# ProProject_NAFA_AstrAlim_2024-01-08.net
KiCad netlist of a schematic drawn in EasyEDA Pro
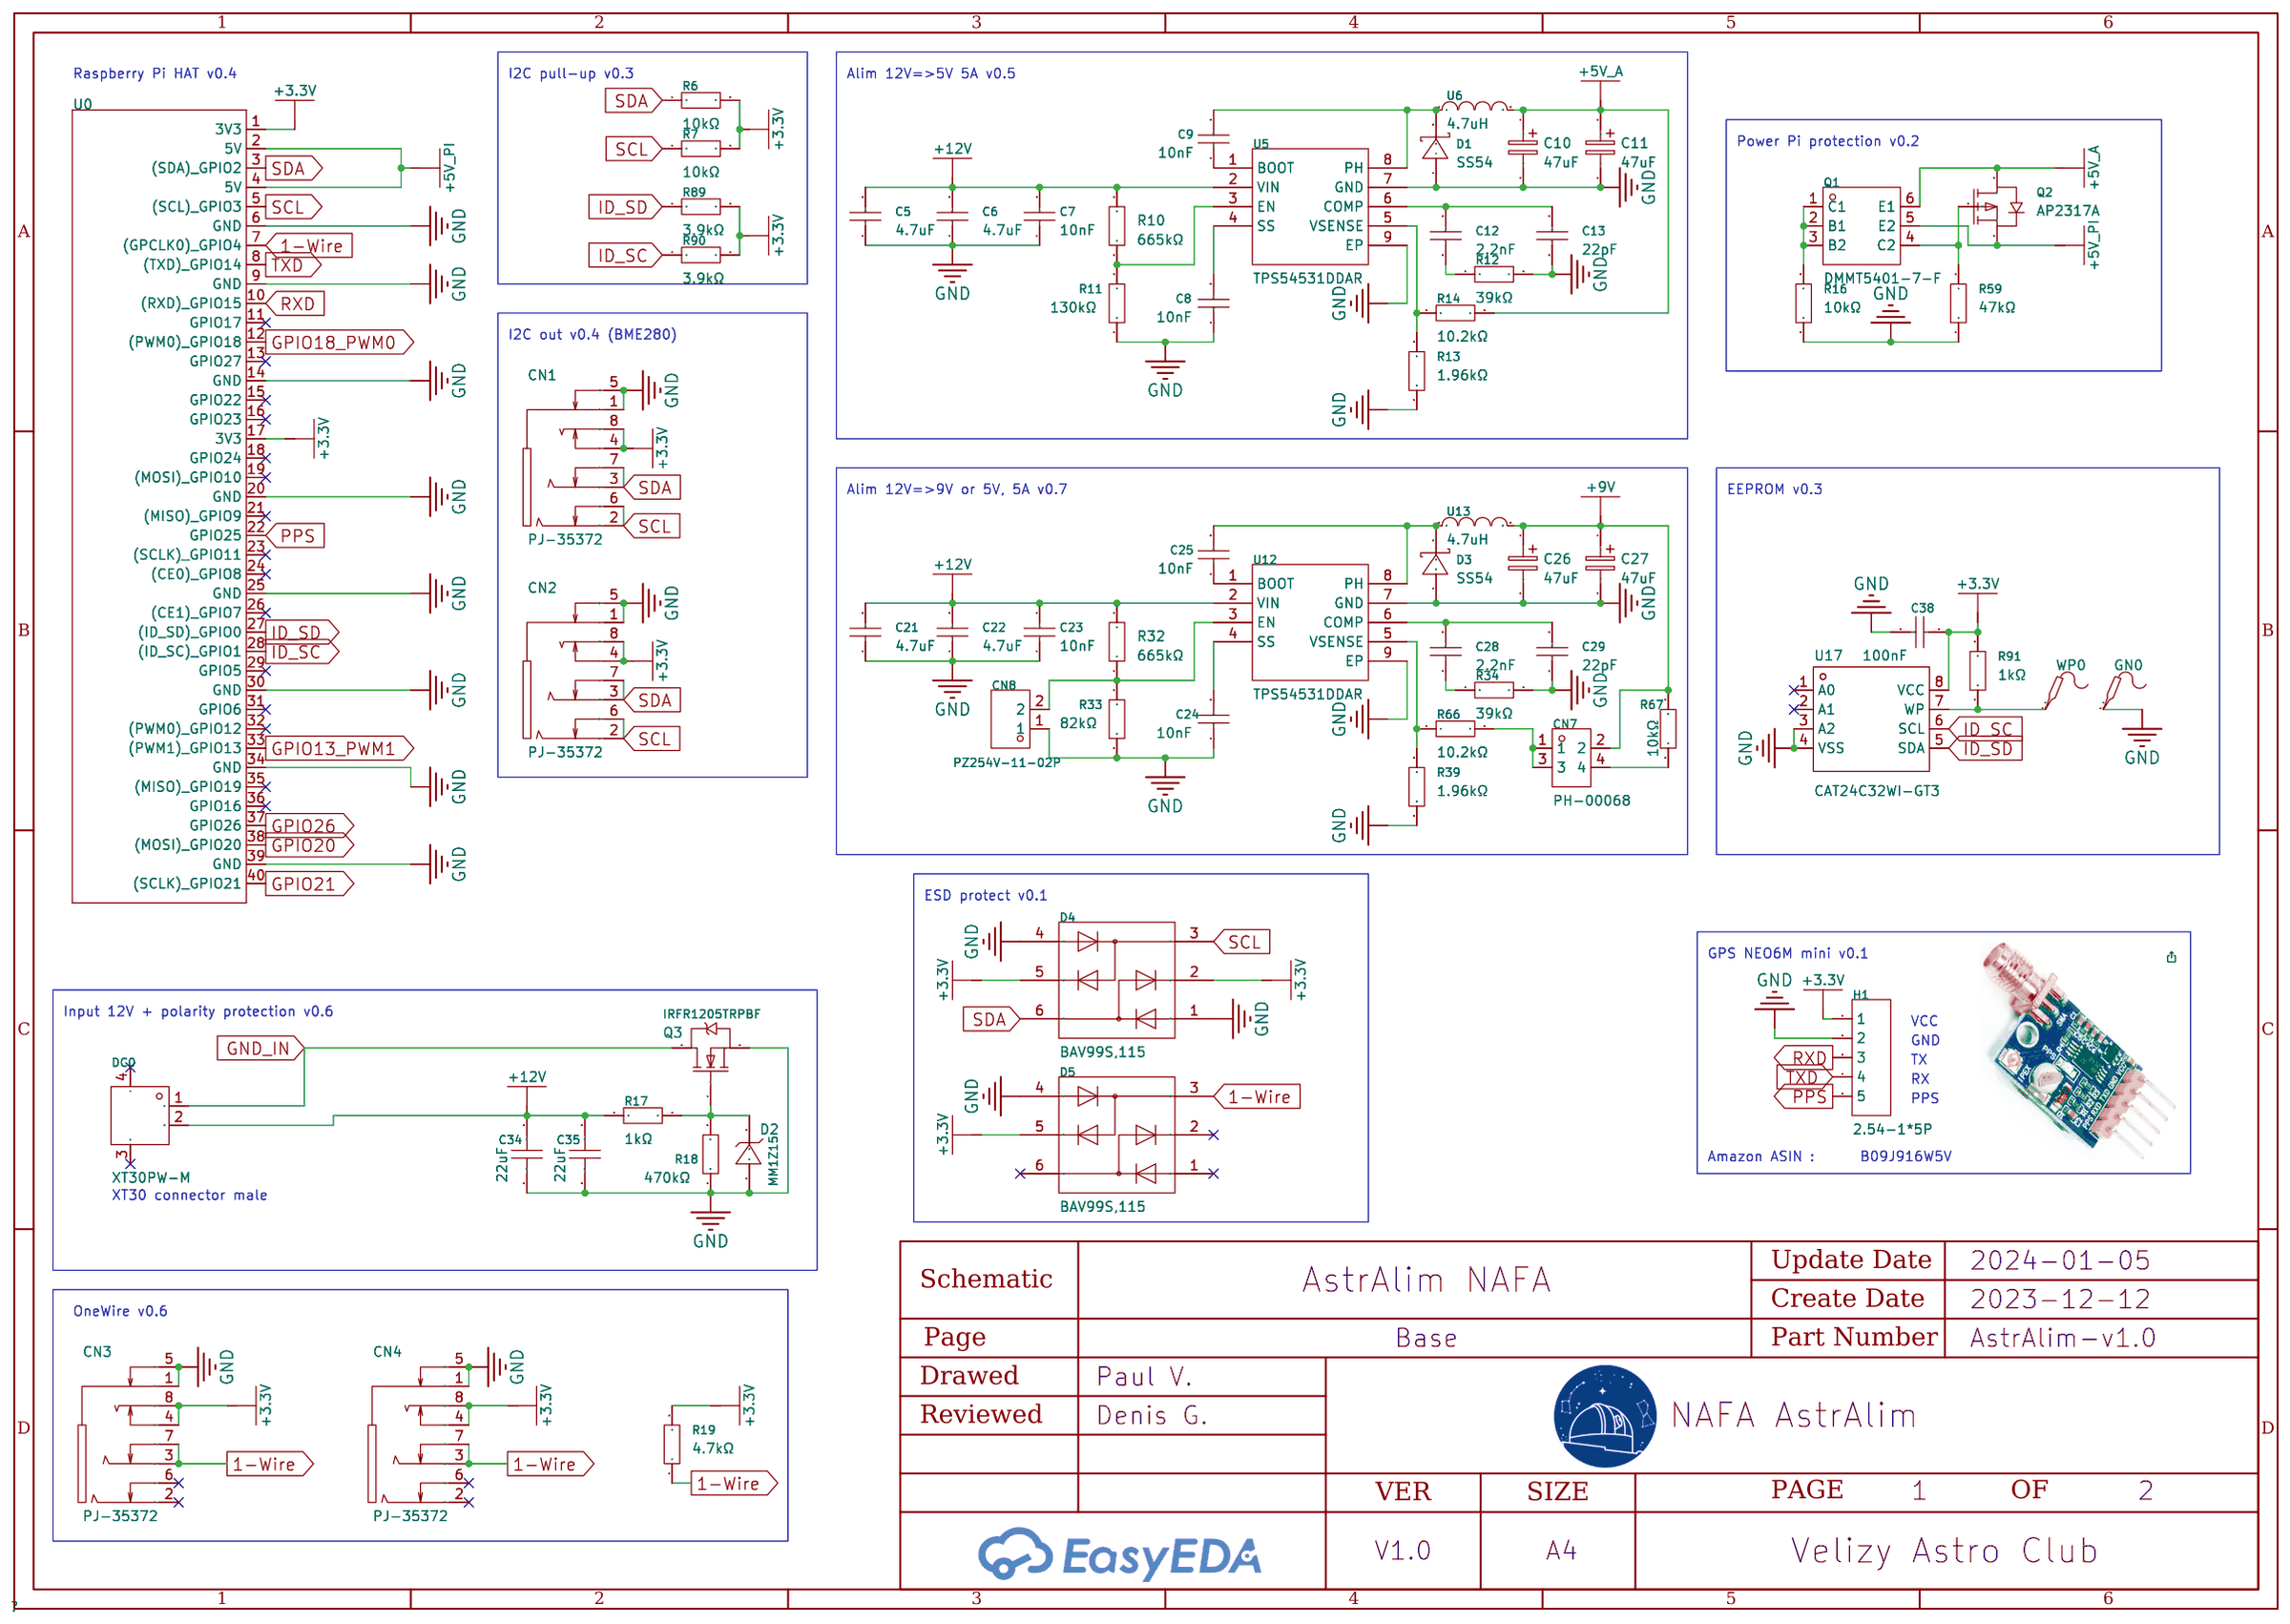
[diagram p0: Base]
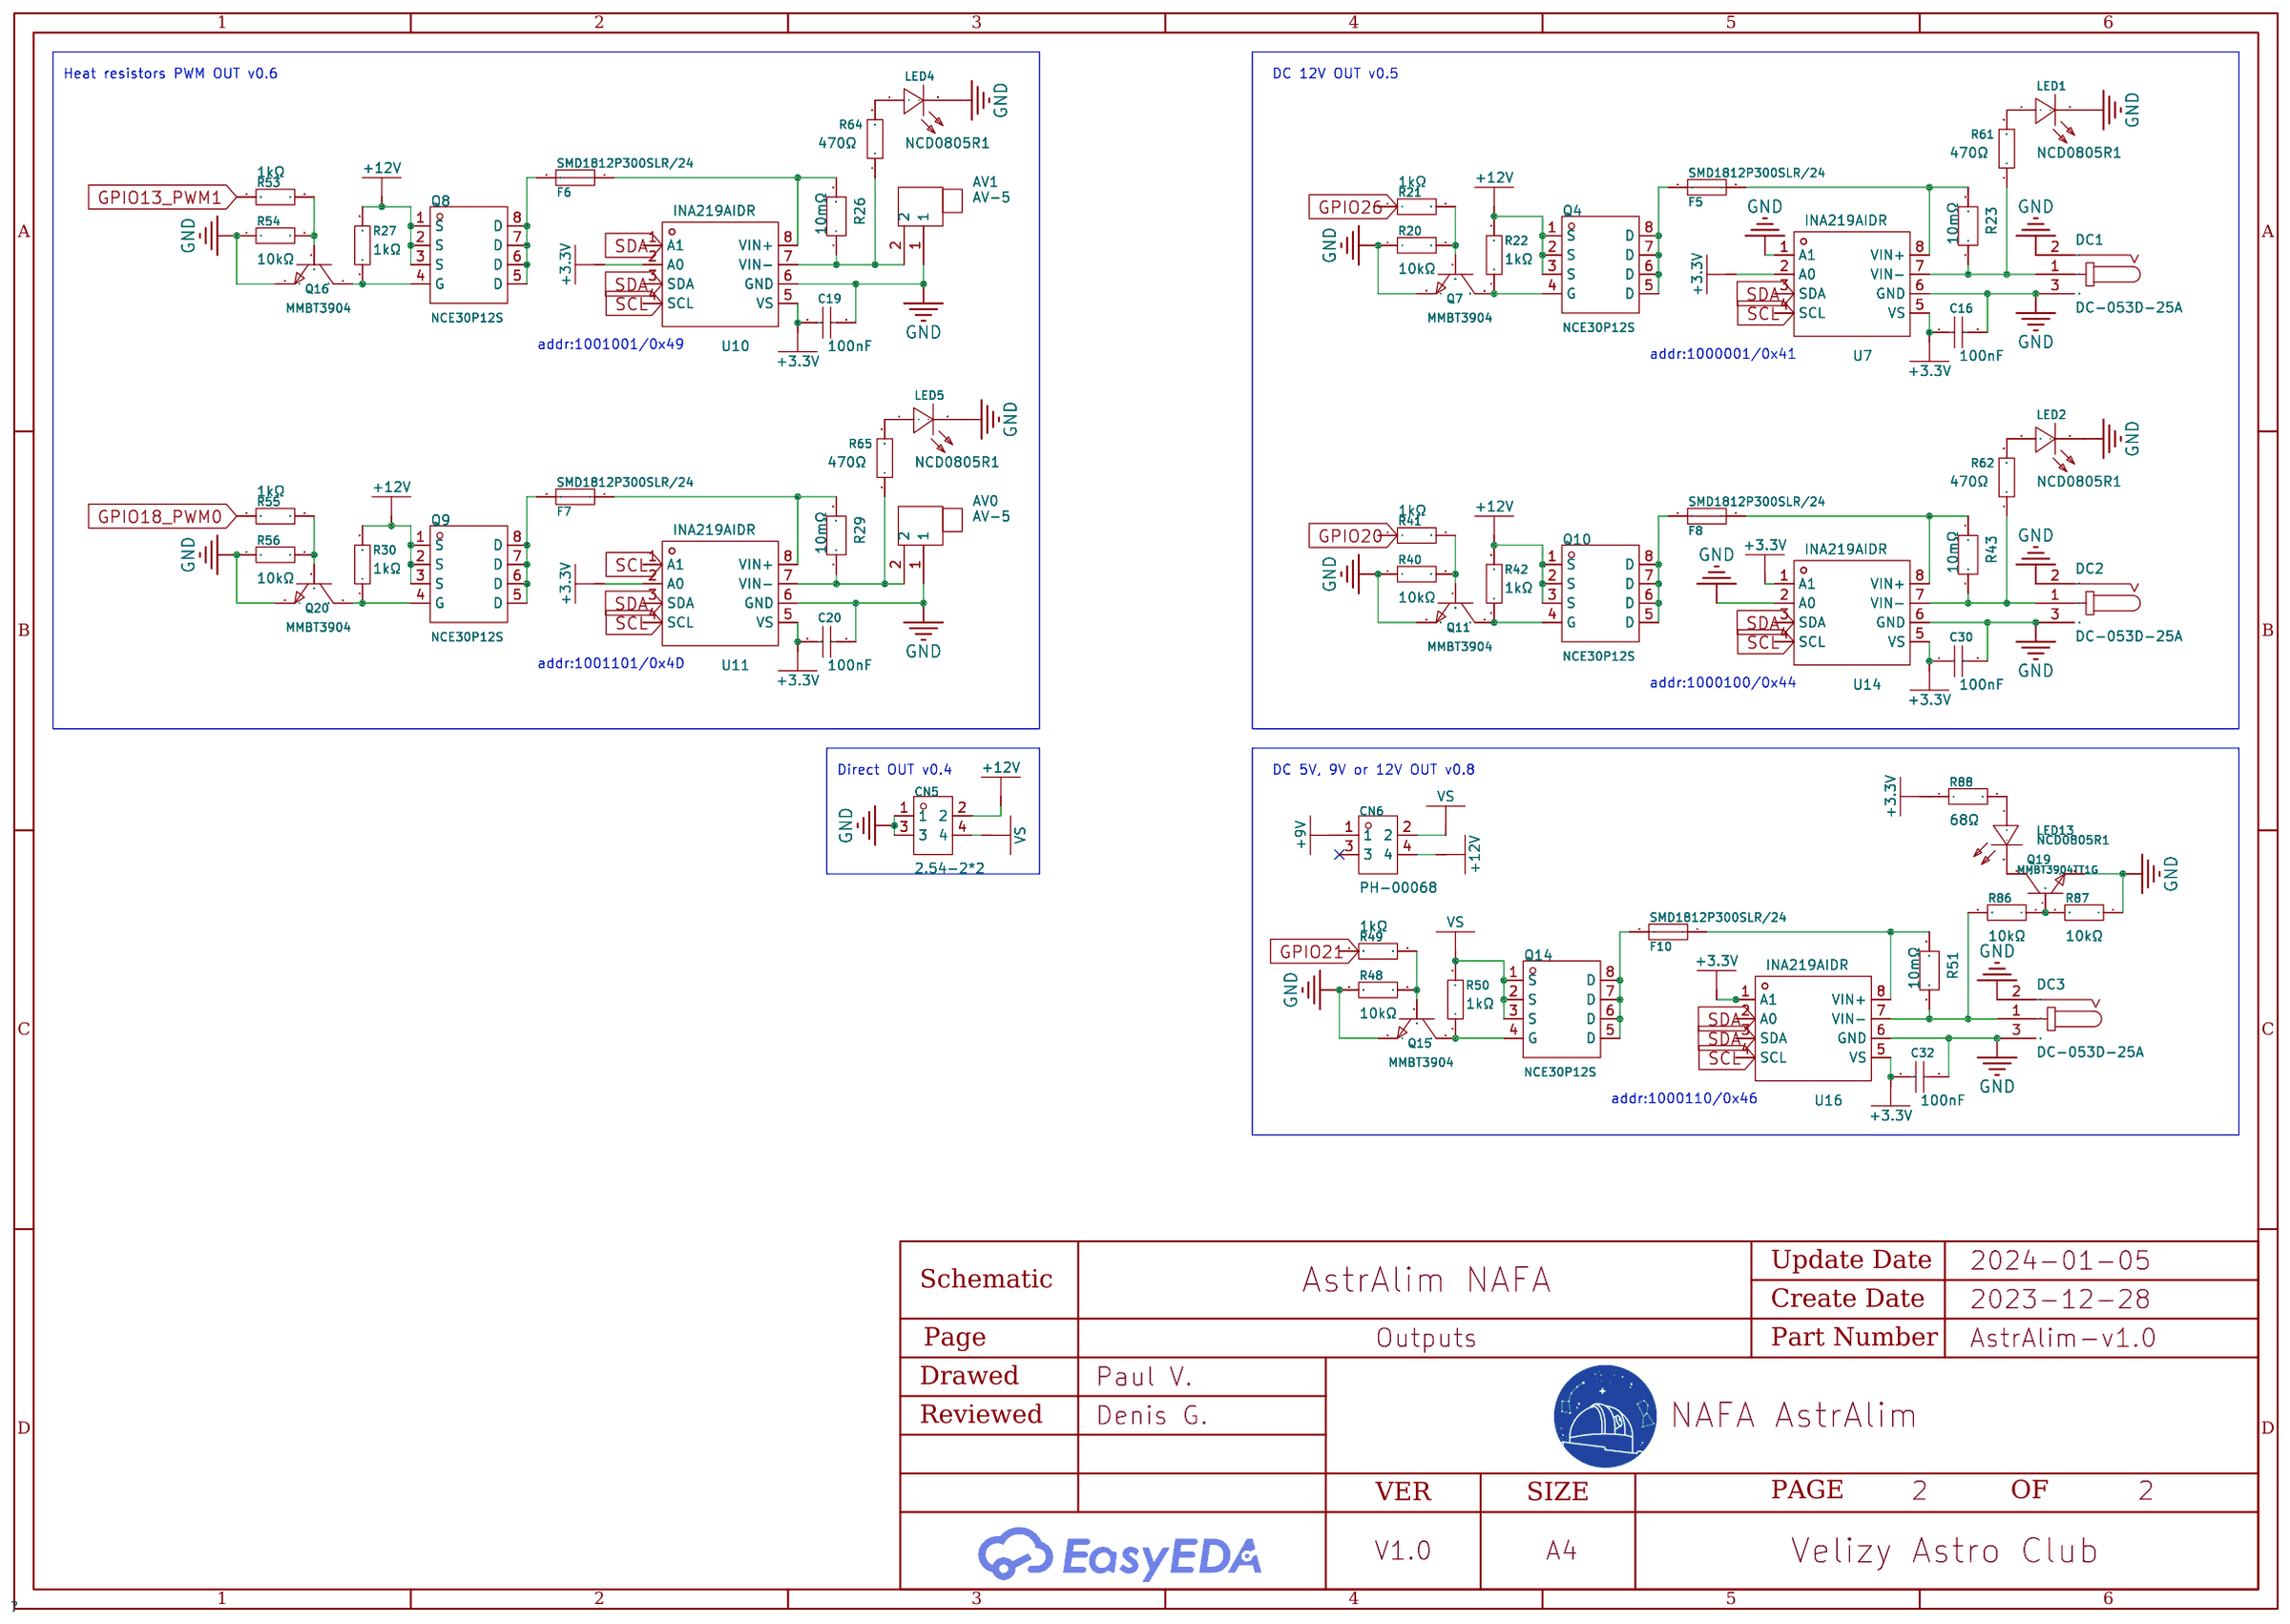
[diagram p1: Outputs]

(export (version "E")
  (design (tool "Eeschema 10.0.6"))
  (components
    (comp (ref "C5")
      (value "4.7uF")
      (footprint "easyedapro:C0805")
      (fields
        (field (name "Manufacturer Part") "CL21A475KAQNNNE")
        (field (name "Manufacturer") "SAMSUNG(三星)")
      )
      (libsource (lib "easyedapro") (part "CL21A475KAQNNNE"))
    )
    (comp (ref "C6")
      (value "4.7uF")
      (footprint "easyedapro:C0805")
      (fields
        (field (name "Manufacturer Part") "CL21A475KAQNNNE")
        (field (name "Manufacturer") "SAMSUNG(三星)")
      )
      (libsource (lib "easyedapro") (part "CL21A475KAQNNNE"))
    )
    (comp (ref "C7")
      (value "10nF")
      (footprint "easyedapro:C0402")
      (fields
        (field (name "Manufacturer Part") "CL05B103KB5NNNC")
        (field (name "Manufacturer") "SAMSUNG(三星)")
      )
      (libsource (lib "easyedapro") (part "CL05B103KB5NNNC"))
    )
    (comp (ref "C8")
      (value "10nF")
      (footprint "easyedapro:C0402")
      (fields
        (field (name "Manufacturer Part") "CL05B103KB5NNNC")
        (field (name "Manufacturer") "SAMSUNG(三星)")
      )
      (libsource (lib "easyedapro") (part "CL05B103KB5NNNC"))
    )
    (comp (ref "C9")
      (value "10nF")
      (footprint "easyedapro:C0402")
      (fields
        (field (name "Manufacturer Part") "CL05B103KB5NNNC")
        (field (name "Manufacturer") "SAMSUNG(三星)")
      )
      (libsource (lib "easyedapro") (part "CL05B103KB5NNNC"))
    )
    (comp (ref "C10")
      (value "47uF")
      (footprint "easyedapro:CAP-SMD_L3.5-W2.8-R-RD")
      (fields
        (field (name "Manufacturer Part") "CA45-B-16V-47uF-K")
        (field (name "Manufacturer") "CEC(振华新云)")
      )
      (libsource (lib "easyedapro") (part "CA45-B-16V-47UF-K"))
    )
    (comp (ref "C11")
      (value "47uF")
      (footprint "easyedapro:CAP-SMD_L3.5-W2.8-R-RD")
      (fields
        (field (name "Manufacturer Part") "CA45-B-16V-47uF-K")
        (field (name "Manufacturer") "CEC(振华新云)")
      )
      (libsource (lib "easyedapro") (part "CA45-B-16V-47UF-K"))
    )
    (comp (ref "C12")
      (value "2.2nF")
      (footprint "easyedapro:C0603")
      (fields (field (name "Manufacturer Part") "0603B222K500NT") (field (name "Manufacturer") "FH(风华)"))
      (libsource (lib "easyedapro") (part "0603B222K500NT"))
    )
    (comp (ref "C13")
      (value "22pF")
      (footprint "easyedapro:C0402")
      (fields (field (name "Manufacturer Part") "0402CG220J500NT") (field (name "Manufacturer") "FH(风华)"))
      (libsource (lib "easyedapro") (part "0402CG220J500NT"))
    )
    (comp (ref "C21")
      (value "4.7uF")
      (footprint "easyedapro:C0805")
      (fields
        (field (name "Manufacturer Part") "CL21A475KAQNNNE")
        (field (name "Manufacturer") "SAMSUNG(三星)")
      )
      (libsource (lib "easyedapro") (part "CL21A475KAQNNNE"))
    )
    (comp (ref "C22")
      (value "4.7uF")
      (footprint "easyedapro:C0805")
      (fields
        (field (name "Manufacturer Part") "CL21A475KAQNNNE")
        (field (name "Manufacturer") "SAMSUNG(三星)")
      )
      (libsource (lib "easyedapro") (part "CL21A475KAQNNNE"))
    )
    (comp (ref "C23")
      (value "10nF")
      (footprint "easyedapro:C0402")
      (fields
        (field (name "Manufacturer Part") "CL05B103KB5NNNC")
        (field (name "Manufacturer") "SAMSUNG(三星)")
      )
      (libsource (lib "easyedapro") (part "CL05B103KB5NNNC"))
    )
    (comp (ref "C24")
      (value "10nF")
      (footprint "easyedapro:C0402")
      (fields
        (field (name "Manufacturer Part") "CL05B103KB5NNNC")
        (field (name "Manufacturer") "SAMSUNG(三星)")
      )
      (libsource (lib "easyedapro") (part "CL05B103KB5NNNC"))
    )
    (comp (ref "C25")
      (value "10nF")
      (footprint "easyedapro:C0402")
      (fields
        (field (name "Manufacturer Part") "CL05B103KB5NNNC")
        (field (name "Manufacturer") "SAMSUNG(三星)")
      )
      (libsource (lib "easyedapro") (part "CL05B103KB5NNNC"))
    )
    (comp (ref "C26")
      (value "47uF")
      (footprint "easyedapro:CAP-SMD_L3.5-W2.8-R-RD")
      (fields
        (field (name "Manufacturer Part") "CA45-B-16V-47uF-K")
        (field (name "Manufacturer") "CEC(振华新云)")
      )
      (libsource (lib "easyedapro") (part "CA45-B-16V-47UF-K"))
    )
    (comp (ref "C27")
      (value "47uF")
      (footprint "easyedapro:CAP-SMD_L3.5-W2.8-R-RD")
      (fields
        (field (name "Manufacturer Part") "CA45-B-16V-47uF-K")
        (field (name "Manufacturer") "CEC(振华新云)")
      )
      (libsource (lib "easyedapro") (part "CA45-B-16V-47UF-K"))
    )
    (comp (ref "C28")
      (value "2.2nF")
      (footprint "easyedapro:C0603")
      (fields (field (name "Manufacturer Part") "0603B222K500NT") (field (name "Manufacturer") "FH(风华)"))
      (libsource (lib "easyedapro") (part "0603B222K500NT"))
    )
    (comp (ref "C29")
      (value "22pF")
      (footprint "easyedapro:C0402")
      (fields (field (name "Manufacturer Part") "0402CG220J500NT") (field (name "Manufacturer") "FH(风华)"))
      (libsource (lib "easyedapro") (part "0402CG220J500NT"))
    )
    (comp (ref "C34")
      (value "22uF")
      (footprint "easyedapro:C0805")
      (fields
        (field (name "Manufacturer Part") "CL21A226MAQNNNE")
        (field (name "Manufacturer") "SAMSUNG(三星)")
      )
      (libsource (lib "easyedapro") (part "CL21A226MAQNNNE"))
    )
    (comp (ref "C35")
      (value "22uF")
      (footprint "easyedapro:C0805")
      (fields
        (field (name "Manufacturer Part") "CL21A226MAQNNNE")
        (field (name "Manufacturer") "SAMSUNG(三星)")
      )
      (libsource (lib "easyedapro") (part "CL21A226MAQNNNE"))
    )
    (comp (ref "C38")
      (value "100nF")
      (footprint "easyedapro:C0402")
      (fields
        (field (name "Manufacturer Part") "CL05B104KO5NNNC")
        (field (name "Manufacturer") "SAMSUNG(三星)")
      )
      (libsource (lib "easyedapro") (part "CL05B104KO5NNNC"))
    )
    (comp (ref "CN1")
      (value "PJ-35372")
      (footprint "easyedapro:AUDIO-TH_PJ-35372")
      (fields (field (name "Manufacturer") "XKB Connectivity(中国星坤)"))
      (libsource (lib "easyedapro") (part "PJ-35372"))
    )
    (comp (ref "CN2")
      (value "PJ-35372")
      (footprint "easyedapro:AUDIO-TH_PJ-35372")
      (fields (field (name "Manufacturer") "XKB Connectivity(中国星坤)"))
      (libsource (lib "easyedapro") (part "PJ-35372"))
    )
    (comp (ref "CN3")
      (value "PJ-35372")
      (footprint "easyedapro:AUDIO-TH_PJ-35372")
      (fields (field (name "Manufacturer") "XKB Connectivity(中国星坤)"))
      (libsource (lib "easyedapro") (part "PJ-35372"))
    )
    (comp (ref "CN4")
      (value "PJ-35372")
      (footprint "easyedapro:AUDIO-TH_PJ-35372")
      (fields (field (name "Manufacturer") "XKB Connectivity(中国星坤)"))
      (libsource (lib "easyedapro") (part "PJ-35372"))
    )
    (comp (ref "CN7")
      (value "PH-00068")
      (footprint "easyedapro:HDR-TH_4P-P2.54-V-M-R2-C2-S2.54")
      (fields (field (name "Manufacturer") "Liansheng(连盛)"))
      (libsource (lib "easyedapro") (part "PH-00068"))
    )
    (comp (ref "CN8")
      (value "PZ254V-11-02P")
      (footprint "easyedapro:HDR-TH_2P-P2.54-V-M")
      (fields (field (name "Manufacturer") "XFCN(兴飞)"))
      (libsource (lib "easyedapro") (part "PZ254V-11-02P"))
    )
    (comp (ref "D1")
      (value "SS54")
      (footprint "easyedapro:SMA_L4.4-W2.8-LS5.4-R-RD")
      (fields (field (name "Manufacturer") "MDD"))
      (libsource (lib "easyedapro") (part "SS54_C22452"))
    )
    (comp (ref "D2")
      (value "MM1Z15")
      (footprint "easyedapro:SOD-123_L2.7-W1.6-LS3.7-RD")
      (fields (field (name "Manufacturer") "ST(先科)"))
      (libsource (lib "easyedapro") (part "MM1Z15"))
    )
    (comp (ref "D3")
      (value "SS54")
      (footprint "easyedapro:SMA_L4.4-W2.8-LS5.4-R-RD")
      (fields (field (name "Manufacturer") "MDD"))
      (libsource (lib "easyedapro") (part "SS54_C22452"))
    )
    (comp (ref "D4")
      (value "BAV99S,115")
      (footprint "easyedapro:SOT-363_L2.0-W1.3-P0.65-LS2.1-TL")
      (fields (field (name "Manufacturer") "Nexperia(安世)"))
      (libsource (lib "easyedapro") (part "BAV99S,135"))
    )
    (comp (ref "D5")
      (value "BAV99S,115")
      (footprint "easyedapro:SOT-363_L2.0-W1.3-P0.65-LS2.1-TL")
      (fields (field (name "Manufacturer") "Nexperia(安世)"))
      (libsource (lib "easyedapro") (part "BAV99S,135"))
    )
    (comp (ref "DC0")
      (value "XT30PW-M")
      (footprint "easyedapro:CONN-TH_XT30PW-F-1")
      (fields (field (name "Manufacturer") "AMASS(艾迈斯)"))
      (libsource (lib "easyedapro") (part "XT30PW-F"))
    )
    (comp (ref "GN0")
      (value "~")
      (footprint "easyedapro:Test-Point-0.5mm")
      (description "Test Point 测试点")
      (libsource (lib "easyedapro") (part "Test-Point"))
    )
    (comp (ref "H1")
      (value "2.54-1*5P")
      (footprint "easyedapro:HDR-TH_5P-P2.54-V-F")
      (fields (field (name "Manufacturer") "BOOMELE(博穆精密)"))
      (libsource (lib "easyedapro") (part "Header-Female-2.54_1x5"))
    )
    (comp (ref "Q1")
      (value "DMMT5401-7-F")
      (footprint "easyedapro:SOT-23-6_L2.9-W1.6-P0.95-LS2.8-BR")
      (fields (field (name "Manufacturer") "DIODES(美台)"))
      (libsource (lib "easyedapro") (part "DMMT5401-7-F"))
    )
    (comp (ref "Q2")
      (value "AP2317A")
      (footprint "easyedapro:SOT-23-3_L2.9-W1.6-P1.90-LS2.8-BR")
      (fields (field (name "Manufacturer") "ALLPOWER(铨力)"))
      (libsource (lib "easyedapro") (part "AP2317A"))
    )
    (comp (ref "Q3")
      (value "IRFR1205TRPBF")
      (footprint "easyedapro:TO-252-3_L6.5-W5.8-P4.58-BL")
      (fields (field (name "Manufacturer") "Infineon(英飞凌)"))
      (libsource (lib "easyedapro") (part "IRFR1205TRPBF"))
    )
    (comp (ref "R6")
      (value "10kΩ")
      (footprint "easyedapro:R0402")
      (fields
        (field (name "Manufacturer Part") "0402WGF1002TCE")
        (field (name "Manufacturer") "UNI-ROYAL(厚声)")
      )
      (libsource (lib "easyedapro") (part "0402WGF1002TCE"))
    )
    (comp (ref "R7")
      (value "10kΩ")
      (footprint "easyedapro:R0402")
      (fields
        (field (name "Manufacturer Part") "0402WGF1002TCE")
        (field (name "Manufacturer") "UNI-ROYAL(厚声)")
      )
      (libsource (lib "easyedapro") (part "0402WGF1002TCE"))
    )
    (comp (ref "R10")
      (value "665kΩ")
      (footprint "easyedapro:R0603")
      (fields (field (name "Manufacturer Part") "AC0603FR-07665KL") (field (name "Manufacturer") "YAGEO(国巨)"))
      (libsource (lib "easyedapro") (part "AC0603FR-07665KL"))
    )
    (comp (ref "R11")
      (value "130kΩ")
      (footprint "easyedapro:R0603")
      (fields
        (field (name "Manufacturer Part") "0603WAF1303T5E")
        (field (name "Manufacturer") "UNI-ROYAL(厚声)")
      )
      (libsource (lib "easyedapro") (part "0603WAF1303T5E"))
    )
    (comp (ref "R12")
      (value "39kΩ")
      (footprint "easyedapro:R0603")
      (fields
        (field (name "Manufacturer Part") "0603WAF3902T5E")
        (field (name "Manufacturer") "UNI-ROYAL(厚声)")
      )
      (libsource (lib "easyedapro") (part "0603WAF3902T5E"))
    )
    (comp (ref "R13")
      (value "1.96kΩ")
      (footprint "easyedapro:R0402")
      (fields
        (field (name "Manufacturer Part") "0402WGF1961TCE")
        (field (name "Manufacturer") "UNI-ROYAL(厚声)")
      )
      (libsource (lib "easyedapro") (part "0402WGF1961TCE"))
    )
    (comp (ref "R14")
      (value "10.2kΩ")
      (footprint "easyedapro:R0402")
      (fields
        (field (name "Manufacturer Part") "0402WGF1022TCE")
        (field (name "Manufacturer") "UNI-ROYAL(厚声)")
      )
      (libsource (lib "easyedapro") (part "0402WGF1022TCE"))
    )
    (comp (ref "R16")
      (value "10kΩ")
      (footprint "easyedapro:R0402")
      (fields
        (field (name "Manufacturer Part") "0402WGF1002TCE")
        (field (name "Manufacturer") "UNI-ROYAL(厚声)")
      )
      (libsource (lib "easyedapro") (part "0402WGF1002TCE"))
    )
    (comp (ref "R17")
      (value "1kΩ")
      (footprint "easyedapro:R0402")
      (fields
        (field (name "Manufacturer Part") "0402WGF1001TCE")
        (field (name "Manufacturer") "UNI-ROYAL(厚声)")
      )
      (libsource (lib "easyedapro") (part "0402WGF1001TCE"))
    )
    (comp (ref "R18")
      (value "470kΩ")
      (footprint "easyedapro:R0603")
      (fields
        (field (name "Manufacturer Part") "0603WAF4703T5E")
        (field (name "Manufacturer") "UNI-ROYAL(厚声)")
      )
      (libsource (lib "easyedapro") (part "0603WAF4703T5E"))
    )
    (comp (ref "R19")
      (value "4.7kΩ")
      (footprint "easyedapro:R0402")
      (fields
        (field (name "Manufacturer Part") "0402WGF4701TCE")
        (field (name "Manufacturer") "UNI-ROYAL(厚声)")
      )
      (libsource (lib "easyedapro") (part "0402WGF4701TCE"))
    )
    (comp (ref "R32")
      (value "665kΩ")
      (footprint "easyedapro:R0603")
      (fields (field (name "Manufacturer Part") "AC0603FR-07665KL") (field (name "Manufacturer") "YAGEO(国巨)"))
      (libsource (lib "easyedapro") (part "AC0603FR-07665KL"))
    )
    (comp (ref "R33")
      (value "82kΩ")
      (footprint "easyedapro:R0603")
      (fields
        (field (name "Manufacturer Part") "0603WAF8202T5E")
        (field (name "Manufacturer") "UNI-ROYAL(厚声)")
      )
      (libsource (lib "easyedapro") (part "0603WAF8202T5E"))
    )
    (comp (ref "R34")
      (value "39kΩ")
      (footprint "easyedapro:R0603")
      (fields
        (field (name "Manufacturer Part") "0603WAF3902T5E")
        (field (name "Manufacturer") "UNI-ROYAL(厚声)")
      )
      (libsource (lib "easyedapro") (part "0603WAF3902T5E"))
    )
    (comp (ref "R39")
      (value "1.96kΩ")
      (footprint "easyedapro:R0402")
      (fields
        (field (name "Manufacturer Part") "0402WGF1961TCE")
        (field (name "Manufacturer") "UNI-ROYAL(厚声)")
      )
      (libsource (lib "easyedapro") (part "0402WGF1961TCE"))
    )
    (comp (ref "R59")
      (value "47kΩ")
      (footprint "easyedapro:R0402")
      (fields
        (field (name "Manufacturer Part") "0402WGF4702TCE")
        (field (name "Manufacturer") "UNI-ROYAL(厚声)")
      )
      (libsource (lib "easyedapro") (part "0402WGF4702TCE"))
    )
    (comp (ref "R66")
      (value "10.2kΩ")
      (footprint "easyedapro:R0402")
      (fields
        (field (name "Manufacturer Part") "0402WGF1022TCE")
        (field (name "Manufacturer") "UNI-ROYAL(厚声)")
      )
      (libsource (lib "easyedapro") (part "0402WGF1022TCE"))
    )
    (comp (ref "R67")
      (value "10kΩ")
      (footprint "easyedapro:R0402")
      (fields
        (field (name "Manufacturer Part") "0402WGF1002TCE")
        (field (name "Manufacturer") "UNI-ROYAL(厚声)")
      )
      (libsource (lib "easyedapro") (part "0402WGF1002TCE"))
    )
    (comp (ref "R89")
      (value "3.9kΩ")
      (footprint "easyedapro:R0603")
      (fields
        (field (name "Manufacturer Part") "0603WAF3901T5E")
        (field (name "Manufacturer") "UNI-ROYAL(厚声)")
      )
      (libsource (lib "easyedapro") (part "0603WAF3901T5E"))
    )
    (comp (ref "R90")
      (value "3.9kΩ")
      (footprint "easyedapro:R0603")
      (fields
        (field (name "Manufacturer Part") "0603WAF3901T5E")
        (field (name "Manufacturer") "UNI-ROYAL(厚声)")
      )
      (libsource (lib "easyedapro") (part "0603WAF3901T5E"))
    )
    (comp (ref "R91")
      (value "1kΩ")
      (footprint "easyedapro:R0402")
      (fields
        (field (name "Manufacturer Part") "0402WGF1001TCE")
        (field (name "Manufacturer") "UNI-ROYAL(厚声)")
      )
      (libsource (lib "easyedapro") (part "0402WGF1001TCE"))
    )
    (comp (ref "U0")
      (value "RASPI HAT FULL")
      (fields (field (name "Manufacturer Part") "RaspberryPi 3"))
      (libsource (lib "easyedapro") (part "RASPI HAT FULL - NO OUTLINE"))
    )
    (comp (ref "U5")
      (value "TPS54531DDAR")
      (footprint "easyedapro:SOIC-8_L5.0-W4.0-P1.27-LS6.0-BL-EP2.0")
      (fields (field (name "Manufacturer") "TI(德州仪器)"))
      (libsource (lib "easyedapro") (part "TPS54531DDAR"))
    )
    (comp (ref "U6")
      (value "4.7uH")
      (footprint "easyedapro:IND-SMD_L7.2-W6.6_GPSR07X0")
      (description "Inductance: Tolerance:±20% Tolerance:±20% Rated Current: DC Resistance (DCR):34.5mΩ")
      (fields (field (name "Manufacturer Part") "CYA0630-4.7UH") (field (name "Manufacturer") "SHOU HAN(首韩)"))
      (libsource (lib "easyedapro") (part "CYA0630-4.7UH"))
    )
    (comp (ref "U12")
      (value "TPS54531DDAR")
      (footprint "easyedapro:SOIC-8_L5.0-W4.0-P1.27-LS6.0-BL-EP2.0")
      (fields (field (name "Manufacturer") "TI(德州仪器)"))
      (libsource (lib "easyedapro") (part "TPS54531DDAR"))
    )
    (comp (ref "U13")
      (value "4.7uH")
      (footprint "easyedapro:IND-SMD_L7.2-W6.6_GPSR07X0")
      (description "Inductance: Tolerance:±20% Tolerance:±20% Rated Current: DC Resistance (DCR):34.5mΩ")
      (fields (field (name "Manufacturer Part") "CYA0630-4.7UH") (field (name "Manufacturer") "SHOU HAN(首韩)"))
      (libsource (lib "easyedapro") (part "CYA0630-4.7UH"))
    )
    (comp (ref "U17")
      (value "CAT24C32WI-GT3")
      (footprint "easyedapro:SOIC-8_L5.0-W4.0-P1.27-LS6.0-BL")
      (fields (field (name "Manufacturer") "onsemi(安森美)"))
      (libsource (lib "easyedapro") (part "CAT24C32WI-GT3"))
    )
    (comp (ref "WP0")
      (value "~")
      (footprint "easyedapro:Test-Point-0.5mm")
      (description "Test Point 测试点")
      (libsource (lib "easyedapro") (part "Test-Point"))
    )
    (comp (ref "AV0")
      (value "AV-5")
      (footprint "easyedapro:CONN-TH_AV-5")
      (fields (field (name "Manufacturer") "BOOMELE(博穆精密)"))
      (libsource (lib "easyedapro") (part "AV-5"))
    )
    (comp (ref "AV1")
      (value "AV-5")
      (footprint "easyedapro:CONN-TH_AV-5")
      (fields (field (name "Manufacturer") "BOOMELE(博穆精密)"))
      (libsource (lib "easyedapro") (part "AV-5"))
    )
    (comp (ref "C16")
      (value "100nF")
      (footprint "easyedapro:C0402")
      (fields
        (field (name "Manufacturer Part") "CL05B104KO5NNNC")
        (field (name "Manufacturer") "SAMSUNG(三星)")
      )
      (libsource (lib "easyedapro") (part "CL05B104KO5NNNC"))
    )
    (comp (ref "C19")
      (value "100nF")
      (footprint "easyedapro:C0402")
      (fields
        (field (name "Manufacturer Part") "CL05B104KO5NNNC")
        (field (name "Manufacturer") "SAMSUNG(三星)")
      )
      (libsource (lib "easyedapro") (part "CL05B104KO5NNNC"))
    )
    (comp (ref "C20")
      (value "100nF")
      (footprint "easyedapro:C0402")
      (fields
        (field (name "Manufacturer Part") "CL05B104KO5NNNC")
        (field (name "Manufacturer") "SAMSUNG(三星)")
      )
      (libsource (lib "easyedapro") (part "CL05B104KO5NNNC"))
    )
    (comp (ref "C30")
      (value "100nF")
      (footprint "easyedapro:C0402")
      (fields
        (field (name "Manufacturer Part") "CL05B104KO5NNNC")
        (field (name "Manufacturer") "SAMSUNG(三星)")
      )
      (libsource (lib "easyedapro") (part "CL05B104KO5NNNC"))
    )
    (comp (ref "C32")
      (value "100nF")
      (footprint "easyedapro:C0402")
      (fields
        (field (name "Manufacturer Part") "CL05B104KO5NNNC")
        (field (name "Manufacturer") "SAMSUNG(三星)")
      )
      (libsource (lib "easyedapro") (part "CL05B104KO5NNNC"))
    )
    (comp (ref "CN5")
      (value "2.54-2*2")
      (footprint "easyedapro:HDR-TH_4P-P2.54-V-F-R2-C2-S2.54")
      (fields (field (name "Manufacturer") "ZHOURI(洲日)"))
      (libsource (lib "easyedapro") (part "2.54-2*2"))
    )
    (comp (ref "CN6")
      (value "PH-00068")
      (footprint "easyedapro:HDR-TH_4P-P2.54-V-M-R2-C2-S2.54")
      (fields (field (name "Manufacturer") "Liansheng(连盛)"))
      (libsource (lib "easyedapro") (part "PH-00068"))
    )
    (comp (ref "DC1")
      (value "DC-053D-25A")
      (footprint "easyedapro:DC-IN-TH_DC-053D-25A-1")
      (fields (field (name "Manufacturer") "韩国韩荣"))
      (libsource (lib "easyedapro") (part "DC-053D-25A"))
    )
    (comp (ref "DC2")
      (value "DC-053D-25A")
      (footprint "easyedapro:DC-IN-TH_DC-053D-25A-1")
      (fields (field (name "Manufacturer") "韩国韩荣"))
      (libsource (lib "easyedapro") (part "DC-053D-25A"))
    )
    (comp (ref "DC3")
      (value "DC-053D-25A")
      (footprint "easyedapro:DC-IN-TH_DC-053D-25A-1")
      (fields (field (name "Manufacturer") "韩国韩荣"))
      (libsource (lib "easyedapro") (part "DC-053D-25A"))
    )
    (comp (ref "F5")
      (value "SMD1812P300SLR/24")
      (footprint "easyedapro:F1812")
      (fields (field (name "Manufacturer") "PTTC(聚鼎)"))
      (libsource (lib "easyedapro") (part "SMD1812P300SLR/24_C2892380"))
    )
    (comp (ref "F6")
      (value "SMD1812P300SLR/24")
      (footprint "easyedapro:F1812")
      (fields (field (name "Manufacturer") "PTTC(聚鼎)"))
      (libsource (lib "easyedapro") (part "SMD1812P300SLR/24_C2892380"))
    )
    (comp (ref "F7")
      (value "SMD1812P300SLR/24")
      (footprint "easyedapro:F1812")
      (fields (field (name "Manufacturer") "PTTC(聚鼎)"))
      (libsource (lib "easyedapro") (part "SMD1812P300SLR/24_C2892380"))
    )
    (comp (ref "F8")
      (value "SMD1812P300SLR/24")
      (footprint "easyedapro:F1812")
      (fields (field (name "Manufacturer") "PTTC(聚鼎)"))
      (libsource (lib "easyedapro") (part "SMD1812P300SLR/24_C2892380"))
    )
    (comp (ref "F10")
      (value "SMD1812P300SLR/24")
      (footprint "easyedapro:F1812")
      (fields (field (name "Manufacturer") "PTTC(聚鼎)"))
      (libsource (lib "easyedapro") (part "SMD1812P300SLR/24_C2892380"))
    )
    (comp (ref "LED1")
      (value "NCD0805R1")
      (footprint "easyedapro:LED0805-R-RD")
      (fields (field (name "Manufacturer") "国星光电"))
      (libsource (lib "easyedapro") (part "FC-2012HRK-620D"))
    )
    (comp (ref "LED2")
      (value "NCD0805R1")
      (footprint "easyedapro:LED0805-R-RD")
      (fields (field (name "Manufacturer") "国星光电"))
      (libsource (lib "easyedapro") (part "FC-2012HRK-620D"))
    )
    (comp (ref "LED4")
      (value "NCD0805R1")
      (footprint "easyedapro:LED0805-R-RD")
      (fields (field (name "Manufacturer") "国星光电"))
      (libsource (lib "easyedapro") (part "FC-2012HRK-620D"))
    )
    (comp (ref "LED5")
      (value "NCD0805R1")
      (footprint "easyedapro:LED0805-R-RD")
      (fields (field (name "Manufacturer") "国星光电"))
      (libsource (lib "easyedapro") (part "FC-2012HRK-620D"))
    )
    (comp (ref "LED13")
      (value "NCD0805R1")
      (footprint "easyedapro:LED0805-R-RD")
      (fields (field (name "Manufacturer") "国星光电"))
      (libsource (lib "easyedapro") (part "FC-2012HRK-620D"))
    )
    (comp (ref "Q4")
      (value "NCE30P12S")
      (footprint "easyedapro:SOIC-8_L4.9-W3.9-P1.27-LS6.0-BL")
      (fields (field (name "Manufacturer") "NCE(无锡新洁能)"))
      (libsource (lib "easyedapro") (part "NCE30P12S"))
    )
    (comp (ref "Q7")
      (value "MMBT3904")
      (footprint "easyedapro:SOT-23-3_L2.9-W1.3-P1.90-LS2.4-BR")
      (fields (field (name "Manufacturer") "CJ(江苏长电/长晶)"))
      (libsource (lib "easyedapro") (part "MMBT3904"))
    )
    (comp (ref "Q8")
      (value "NCE30P12S")
      (footprint "easyedapro:SOIC-8_L4.9-W3.9-P1.27-LS6.0-BL")
      (fields (field (name "Manufacturer") "NCE(无锡新洁能)"))
      (libsource (lib "easyedapro") (part "NCE30P12S"))
    )
    (comp (ref "Q9")
      (value "NCE30P12S")
      (footprint "easyedapro:SOIC-8_L4.9-W3.9-P1.27-LS6.0-BL")
      (fields (field (name "Manufacturer") "NCE(无锡新洁能)"))
      (libsource (lib "easyedapro") (part "NCE30P12S"))
    )
    (comp (ref "Q10")
      (value "NCE30P12S")
      (footprint "easyedapro:SOIC-8_L4.9-W3.9-P1.27-LS6.0-BL")
      (fields (field (name "Manufacturer") "NCE(无锡新洁能)"))
      (libsource (lib "easyedapro") (part "NCE30P12S"))
    )
    (comp (ref "Q11")
      (value "MMBT3904")
      (footprint "easyedapro:SOT-23-3_L2.9-W1.3-P1.90-LS2.4-BR")
      (fields (field (name "Manufacturer") "CJ(江苏长电/长晶)"))
      (libsource (lib "easyedapro") (part "MMBT3904"))
    )
    (comp (ref "Q14")
      (value "NCE30P12S")
      (footprint "easyedapro:SOIC-8_L4.9-W3.9-P1.27-LS6.0-BL")
      (fields (field (name "Manufacturer") "NCE(无锡新洁能)"))
      (libsource (lib "easyedapro") (part "NCE30P12S"))
    )
    (comp (ref "Q15")
      (value "MMBT3904")
      (footprint "easyedapro:SOT-23-3_L2.9-W1.3-P1.90-LS2.4-BR")
      (fields (field (name "Manufacturer") "CJ(江苏长电/长晶)"))
      (libsource (lib "easyedapro") (part "MMBT3904"))
    )
    (comp (ref "Q16")
      (value "MMBT3904")
      (footprint "easyedapro:SOT-23-3_L2.9-W1.3-P1.90-LS2.4-BR")
      (fields (field (name "Manufacturer") "CJ(江苏长电/长晶)"))
      (libsource (lib "easyedapro") (part "MMBT3904"))
    )
    (comp (ref "Q19")
      (value "MMBT3904TT1G")
      (footprint "easyedapro:SC-75-3_L1.6-W0.8-P1.00-LS1.6-BR")
      (fields (field (name "Manufacturer") "onsemi(安森美)"))
      (libsource (lib "easyedapro") (part "MMBT3904TT1G"))
    )
    (comp (ref "Q20")
      (value "MMBT3904")
      (footprint "easyedapro:SOT-23-3_L2.9-W1.3-P1.90-LS2.4-BR")
      (fields (field (name "Manufacturer") "CJ(江苏长电/长晶)"))
      (libsource (lib "easyedapro") (part "MMBT3904"))
    )
    (comp (ref "R20")
      (value "10kΩ")
      (footprint "easyedapro:R0402")
      (fields
        (field (name "Manufacturer Part") "0402WGF1002TCE")
        (field (name "Manufacturer") "UNI-ROYAL(厚声)")
      )
      (libsource (lib "easyedapro") (part "0402WGF1002TCE"))
    )
    (comp (ref "R21")
      (value "1kΩ")
      (footprint "easyedapro:R0402")
      (fields
        (field (name "Manufacturer Part") "0402WGF1001TCE")
        (field (name "Manufacturer") "UNI-ROYAL(厚声)")
      )
      (libsource (lib "easyedapro") (part "0402WGF1001TCE"))
    )
    (comp (ref "R22")
      (value "1kΩ")
      (footprint "easyedapro:R0402")
      (fields
        (field (name "Manufacturer Part") "0402WGF1001TCE")
        (field (name "Manufacturer") "UNI-ROYAL(厚声)")
      )
      (libsource (lib "easyedapro") (part "0402WGF1001TCE"))
    )
    (comp (ref "R23")
      (value "10mΩ")
      (footprint "easyedapro:R1206")
      (fields (field (name "Manufacturer Part") "MFJ06HR010FT") (field (name "Manufacturer") "FH(风华)"))
      (libsource (lib "easyedapro") (part "MFJ06HR010FT"))
    )
    (comp (ref "R26")
      (value "10mΩ")
      (footprint "easyedapro:R1206")
      (fields (field (name "Manufacturer Part") "MFJ06HR010FT") (field (name "Manufacturer") "FH(风华)"))
      (libsource (lib "easyedapro") (part "MFJ06HR010FT"))
    )
    (comp (ref "R27")
      (value "1kΩ")
      (footprint "easyedapro:R0402")
      (fields
        (field (name "Manufacturer Part") "0402WGF1001TCE")
        (field (name "Manufacturer") "UNI-ROYAL(厚声)")
      )
      (libsource (lib "easyedapro") (part "0402WGF1001TCE"))
    )
    (comp (ref "R29")
      (value "10mΩ")
      (footprint "easyedapro:R1206")
      (fields (field (name "Manufacturer Part") "MFJ06HR010FT") (field (name "Manufacturer") "FH(风华)"))
      (libsource (lib "easyedapro") (part "MFJ06HR010FT"))
    )
    (comp (ref "R30")
      (value "1kΩ")
      (footprint "easyedapro:R0402")
      (fields
        (field (name "Manufacturer Part") "0402WGF1001TCE")
        (field (name "Manufacturer") "UNI-ROYAL(厚声)")
      )
      (libsource (lib "easyedapro") (part "0402WGF1001TCE"))
    )
    (comp (ref "R40")
      (value "10kΩ")
      (footprint "easyedapro:R0402")
      (fields
        (field (name "Manufacturer Part") "0402WGF1002TCE")
        (field (name "Manufacturer") "UNI-ROYAL(厚声)")
      )
      (libsource (lib "easyedapro") (part "0402WGF1002TCE"))
    )
    (comp (ref "R41")
      (value "1kΩ")
      (footprint "easyedapro:R0402")
      (fields
        (field (name "Manufacturer Part") "0402WGF1001TCE")
        (field (name "Manufacturer") "UNI-ROYAL(厚声)")
      )
      (libsource (lib "easyedapro") (part "0402WGF1001TCE"))
    )
    (comp (ref "R42")
      (value "1kΩ")
      (footprint "easyedapro:R0402")
      (fields
        (field (name "Manufacturer Part") "0402WGF1001TCE")
        (field (name "Manufacturer") "UNI-ROYAL(厚声)")
      )
      (libsource (lib "easyedapro") (part "0402WGF1001TCE"))
    )
    (comp (ref "R43")
      (value "10mΩ")
      (footprint "easyedapro:R1206")
      (fields (field (name "Manufacturer Part") "MFJ06HR010FT") (field (name "Manufacturer") "FH(风华)"))
      (libsource (lib "easyedapro") (part "MFJ06HR010FT"))
    )
    (comp (ref "R48")
      (value "10kΩ")
      (footprint "easyedapro:R0402")
      (fields
        (field (name "Manufacturer Part") "0402WGF1002TCE")
        (field (name "Manufacturer") "UNI-ROYAL(厚声)")
      )
      (libsource (lib "easyedapro") (part "0402WGF1002TCE"))
    )
    (comp (ref "R49")
      (value "1kΩ")
      (footprint "easyedapro:R0402")
      (fields
        (field (name "Manufacturer Part") "0402WGF1001TCE")
        (field (name "Manufacturer") "UNI-ROYAL(厚声)")
      )
      (libsource (lib "easyedapro") (part "0402WGF1001TCE"))
    )
    (comp (ref "R50")
      (value "1kΩ")
      (footprint "easyedapro:R0402")
      (fields
        (field (name "Manufacturer Part") "0402WGF1001TCE")
        (field (name "Manufacturer") "UNI-ROYAL(厚声)")
      )
      (libsource (lib "easyedapro") (part "0402WGF1001TCE"))
    )
    (comp (ref "R51")
      (value "10mΩ")
      (footprint "easyedapro:R1206")
      (fields (field (name "Manufacturer Part") "MFJ06HR010FT") (field (name "Manufacturer") "FH(风华)"))
      (libsource (lib "easyedapro") (part "MFJ06HR010FT"))
    )
    (comp (ref "R53")
      (value "1kΩ")
      (footprint "easyedapro:R0402")
      (fields
        (field (name "Manufacturer Part") "0402WGF1001TCE")
        (field (name "Manufacturer") "UNI-ROYAL(厚声)")
      )
      (libsource (lib "easyedapro") (part "0402WGF1001TCE"))
    )
    (comp (ref "R54")
      (value "10kΩ")
      (footprint "easyedapro:R0402")
      (fields
        (field (name "Manufacturer Part") "0402WGF1002TCE")
        (field (name "Manufacturer") "UNI-ROYAL(厚声)")
      )
      (libsource (lib "easyedapro") (part "0402WGF1002TCE"))
    )
    (comp (ref "R55")
      (value "1kΩ")
      (footprint "easyedapro:R0402")
      (fields
        (field (name "Manufacturer Part") "0402WGF1001TCE")
        (field (name "Manufacturer") "UNI-ROYAL(厚声)")
      )
      (libsource (lib "easyedapro") (part "0402WGF1001TCE"))
    )
    (comp (ref "R56")
      (value "10kΩ")
      (footprint "easyedapro:R0402")
      (fields
        (field (name "Manufacturer Part") "0402WGF1002TCE")
        (field (name "Manufacturer") "UNI-ROYAL(厚声)")
      )
      (libsource (lib "easyedapro") (part "0402WGF1002TCE"))
    )
    (comp (ref "R61")
      (value "470Ω")
      (footprint "easyedapro:R0402")
      (fields
        (field (name "Manufacturer Part") "0402WGF4700TCE")
        (field (name "Manufacturer") "UNI-ROYAL(厚声)")
      )
      (libsource (lib "easyedapro") (part "0402WGF4700TCE"))
    )
    (comp (ref "R62")
      (value "470Ω")
      (footprint "easyedapro:R0402")
      (fields
        (field (name "Manufacturer Part") "0402WGF4700TCE")
        (field (name "Manufacturer") "UNI-ROYAL(厚声)")
      )
      (libsource (lib "easyedapro") (part "0402WGF4700TCE"))
    )
    (comp (ref "R64")
      (value "470Ω")
      (footprint "easyedapro:R0402")
      (fields
        (field (name "Manufacturer Part") "0402WGF4700TCE")
        (field (name "Manufacturer") "UNI-ROYAL(厚声)")
      )
      (libsource (lib "easyedapro") (part "0402WGF4700TCE"))
    )
    (comp (ref "R65")
      (value "470Ω")
      (footprint "easyedapro:R0402")
      (fields
        (field (name "Manufacturer Part") "0402WGF4700TCE")
        (field (name "Manufacturer") "UNI-ROYAL(厚声)")
      )
      (libsource (lib "easyedapro") (part "0402WGF4700TCE"))
    )
    (comp (ref "R86")
      (value "10kΩ")
      (footprint "easyedapro:R0402")
      (fields
        (field (name "Manufacturer Part") "0402WGF1002TCE")
        (field (name "Manufacturer") "UNI-ROYAL(厚声)")
      )
      (libsource (lib "easyedapro") (part "0402WGF1002TCE"))
    )
    (comp (ref "R87")
      (value "10kΩ")
      (footprint "easyedapro:R0402")
      (fields
        (field (name "Manufacturer Part") "0402WGF1002TCE")
        (field (name "Manufacturer") "UNI-ROYAL(厚声)")
      )
      (libsource (lib "easyedapro") (part "0402WGF1002TCE"))
    )
    (comp (ref "R88")
      (value "68Ω")
      (footprint "easyedapro:R0603")
      (fields
        (field (name "Manufacturer Part") "0603WAF680JT5E")
        (field (name "Manufacturer") "UNI-ROYAL(厚声)")
      )
      (libsource (lib "easyedapro") (part "0603WAF680JT5E"))
    )
    (comp (ref "U7")
      (value "INA219AIDR")
      (footprint "easyedapro:SOIC-8_L4.9-W3.9-P1.27-LS6.0-BL")
      (fields (field (name "Manufacturer") "TI(德州仪器)"))
      (libsource (lib "easyedapro") (part "INA219AIDR"))
    )
    (comp (ref "U10")
      (value "INA219AIDR")
      (footprint "easyedapro:SOIC-8_L4.9-W3.9-P1.27-LS6.0-BL")
      (fields (field (name "Manufacturer") "TI(德州仪器)"))
      (libsource (lib "easyedapro") (part "INA219AIDR"))
    )
    (comp (ref "U11")
      (value "INA219AIDR")
      (footprint "easyedapro:SOIC-8_L4.9-W3.9-P1.27-LS6.0-BL")
      (fields (field (name "Manufacturer") "TI(德州仪器)"))
      (libsource (lib "easyedapro") (part "INA219AIDR"))
    )
    (comp (ref "U14")
      (value "INA219AIDR")
      (footprint "easyedapro:SOIC-8_L4.9-W3.9-P1.27-LS6.0-BL")
      (fields (field (name "Manufacturer") "TI(德州仪器)"))
      (libsource (lib "easyedapro") (part "INA219AIDR"))
    )
    (comp (ref "U16")
      (value "INA219AIDR")
      (footprint "easyedapro:SOIC-8_L4.9-W3.9-P1.27-LS6.0-BL")
      (fields (field (name "Manufacturer") "TI(德州仪器)"))
      (libsource (lib "easyedapro") (part "INA219AIDR"))
    )
  )
  (nets
    (net (code "1") (name "+3.3V") (class "Default")
      (node (ref "C16") (pin "1") (pinfunction "1_1") (pintype "input"))
      (node (ref "C19") (pin "1") (pinfunction "1_1") (pintype "input"))
      (node (ref "C20") (pin "1") (pinfunction "1_1") (pintype "input"))
      (node (ref "C30") (pin "1") (pinfunction "1_1") (pintype "input"))
      (node (ref "C32") (pin "1") (pinfunction "1_1") (pintype "input"))
      (node (ref "C38") (pin "2") (pinfunction "2_2") (pintype "input"))
      (node (ref "CN1") (pin "4") (pinfunction "4_4") (pintype "input"))
      (node (ref "CN1") (pin "8") (pinfunction "8_8") (pintype "input"))
      (node (ref "CN2") (pin "4") (pinfunction "4_4") (pintype "input"))
      (node (ref "CN2") (pin "8") (pinfunction "8_8") (pintype "input"))
      (node (ref "CN3") (pin "4") (pinfunction "4_4") (pintype "input"))
      (node (ref "CN3") (pin "8") (pinfunction "8_8") (pintype "input"))
      (node (ref "CN4") (pin "4") (pinfunction "4_4") (pintype "input"))
      (node (ref "CN4") (pin "8") (pinfunction "8_8") (pintype "input"))
      (node (ref "D4") (pin "2") (pinfunction "C_2") (pintype "input"))
      (node (ref "D4") (pin "5") (pinfunction "C_5") (pintype "input"))
      (node (ref "D5") (pin "5") (pinfunction "C_5") (pintype "input"))
      (node (ref "H1") (pin "1") (pinfunction "1_1") (pintype "input"))
      (node (ref "R19") (pin "2") (pinfunction "2_2") (pintype "input"))
      (node (ref "R6") (pin "2") (pinfunction "2_2") (pintype "input"))
      (node (ref "R7") (pin "2") (pinfunction "2_2") (pintype "input"))
      (node (ref "R88") (pin "1") (pinfunction "1_1") (pintype "input"))
      (node (ref "R89") (pin "2") (pinfunction "2_2") (pintype "input"))
      (node (ref "R90") (pin "2") (pinfunction "2_2") (pintype "input"))
      (node (ref "R91") (pin "2") (pinfunction "2_2") (pintype "input"))
      (node (ref "U0") (pin "1") (pinfunction "3V3_1") (pintype "unspecified"))
      (node (ref "U0") (pin "17") (pinfunction "3V3_17") (pintype "unspecified"))
      (node (ref "U10") (pin "2") (pinfunction "A0_2") (pintype "input"))
      (node (ref "U10") (pin "5") (pinfunction "VS_5") (pintype "input"))
      (node (ref "U11") (pin "2") (pinfunction "A0_2") (pintype "input"))
      (node (ref "U11") (pin "5") (pinfunction "VS_5") (pintype "input"))
      (node (ref "U14") (pin "1") (pinfunction "A1_1") (pintype "input"))
      (node (ref "U14") (pin "5") (pinfunction "VS_5") (pintype "input"))
      (node (ref "U16") (pin "1") (pinfunction "A1_1") (pintype "input"))
      (node (ref "U16") (pin "5") (pinfunction "VS_5") (pintype "input"))
      (node (ref "U17") (pin "8") (pinfunction "VCC_8") (pintype "input"))
      (node (ref "U7") (pin "2") (pinfunction "A0_2") (pintype "input"))
      (node (ref "U7") (pin "5") (pinfunction "VS_5") (pintype "input"))
    )
    (net (code "2") (name "+5V_A") (class "Default")
      (node (ref "C10") (pin "1") (pinfunction "1_1") (pintype "input"))
      (node (ref "C11") (pin "1") (pinfunction "1_1") (pintype "input"))
      (node (ref "Q1") (pin "6") (pinfunction "E1_6") (pintype "input"))
      (node (ref "Q2") (pin "3") (pinfunction "D_3") (pintype "input"))
      (node (ref "R14") (pin "2") (pinfunction "2_2") (pintype "input"))
      (node (ref "U6") (pin "2") (pinfunction "2_2") (pintype "input"))
    )
    (net (code "3") (name "+5V_PI") (class "Default")
      (node (ref "Q1") (pin "5") (pinfunction "E2_5") (pintype "input"))
      (node (ref "Q2") (pin "2") (pinfunction "S_2") (pintype "input"))
      (node (ref "U0") (pin "2") (pinfunction "5V_2") (pintype "unspecified"))
      (node (ref "U0") (pin "4") (pinfunction "5V_4") (pintype "unspecified"))
    )
    (net (code "4") (name "+9V") (class "Default")
      (node (ref "C26") (pin "1") (pinfunction "1_1") (pintype "input"))
      (node (ref "C27") (pin "1") (pinfunction "1_1") (pintype "input"))
      (node (ref "CN6") (pin "1") (pinfunction "1_1") (pintype "input"))
      (node (ref "CN7") (pin "2") (pinfunction "2_2") (pintype "input"))
      (node (ref "R67") (pin "2") (pinfunction "2_2") (pintype "input"))
      (node (ref "U13") (pin "2") (pinfunction "2_2") (pintype "input"))
    )
    (net (code "5") (name "+12V") (class "Default")
      (node (ref "C21") (pin "2") (pinfunction "2_2") (pintype "input"))
      (node (ref "C22") (pin "2") (pinfunction "2_2") (pintype "input"))
      (node (ref "C23") (pin "2") (pinfunction "2_2") (pintype "input"))
      (node (ref "C34") (pin "2") (pinfunction "2_2") (pintype "input"))
      (node (ref "C35") (pin "2") (pinfunction "2_2") (pintype "input"))
      (node (ref "C5") (pin "2") (pinfunction "2_2") (pintype "input"))
      (node (ref "C6") (pin "2") (pinfunction "2_2") (pintype "input"))
      (node (ref "C7") (pin "2") (pinfunction "2_2") (pintype "input"))
      (node (ref "CN5") (pin "2") (pinfunction "2_2") (pintype "input"))
      (node (ref "CN6") (pin "4") (pinfunction "4_4") (pintype "input"))
      (node (ref "DC0") (pin "2") (pinfunction "2_2") (pintype "input"))
      (node (ref "Q10") (pin "1") (pinfunction "S_1") (pintype "input"))
      (node (ref "Q10") (pin "2") (pinfunction "S_2") (pintype "input"))
      (node (ref "Q10") (pin "3") (pinfunction "S_3") (pintype "input"))
      (node (ref "Q4") (pin "1") (pinfunction "S_1") (pintype "input"))
      (node (ref "Q4") (pin "2") (pinfunction "S_2") (pintype "input"))
      (node (ref "Q4") (pin "3") (pinfunction "S_3") (pintype "input"))
      (node (ref "Q8") (pin "1") (pinfunction "S_1") (pintype "input"))
      (node (ref "Q8") (pin "2") (pinfunction "S_2") (pintype "input"))
      (node (ref "Q8") (pin "3") (pinfunction "S_3") (pintype "input"))
      (node (ref "Q9") (pin "1") (pinfunction "S_1") (pintype "input"))
      (node (ref "Q9") (pin "2") (pinfunction "S_2") (pintype "input"))
      (node (ref "Q9") (pin "3") (pinfunction "S_3") (pintype "input"))
      (node (ref "R10") (pin "2") (pinfunction "2_2") (pintype "input"))
      (node (ref "R17") (pin "1") (pinfunction "1_1") (pintype "input"))
      (node (ref "R22") (pin "2") (pinfunction "2_2") (pintype "input"))
      (node (ref "R27") (pin "2") (pinfunction "2_2") (pintype "input"))
      (node (ref "R30") (pin "2") (pinfunction "2_2") (pintype "input"))
      (node (ref "R32") (pin "2") (pinfunction "2_2") (pintype "input"))
      (node (ref "R42") (pin "2") (pinfunction "2_2") (pintype "input"))
      (node (ref "U12") (pin "2") (pinfunction "VIN_2") (pintype "input"))
      (node (ref "U5") (pin "2") (pinfunction "VIN_2") (pintype "input"))
    )
    (net (code "6") (name "1-Wire") (class "Default")
      (node (ref "CN3") (pin "3") (pinfunction "3_3") (pintype "input"))
      (node (ref "CN3") (pin "7") (pinfunction "7_7") (pintype "input"))
      (node (ref "CN4") (pin "3") (pinfunction "3_3") (pintype "input"))
      (node (ref "CN4") (pin "7") (pinfunction "7_7") (pintype "input"))
      (node (ref "D5") (pin "3") (pinfunction "AC_3") (pintype "input"))
      (node (ref "R19") (pin "1") (pinfunction "1_1") (pintype "input"))
      (node (ref "U0") (pin "7") (pinfunction "(GPCLK0)_GPIO4_7") (pintype "unspecified"))
    )
    (net (code "7") (name "GND") (class "Default")
      (node (ref "AV0") (pin "1") (pinfunction "1_1") (pintype "input"))
      (node (ref "AV1") (pin "1") (pinfunction "1_1") (pintype "input"))
      (node (ref "C10") (pin "2") (pinfunction "2_2") (pintype "input"))
      (node (ref "C11") (pin "2") (pinfunction "2_2") (pintype "input"))
      (node (ref "C13") (pin "1") (pinfunction "1_1") (pintype "input"))
      (node (ref "C16") (pin "2") (pinfunction "2_2") (pintype "input"))
      (node (ref "C19") (pin "2") (pinfunction "2_2") (pintype "input"))
      (node (ref "C20") (pin "2") (pinfunction "2_2") (pintype "input"))
      (node (ref "C21") (pin "1") (pinfunction "1_1") (pintype "input"))
      (node (ref "C22") (pin "1") (pinfunction "1_1") (pintype "input"))
      (node (ref "C23") (pin "1") (pinfunction "1_1") (pintype "input"))
      (node (ref "C24") (pin "1") (pinfunction "1_1") (pintype "input"))
      (node (ref "C26") (pin "2") (pinfunction "2_2") (pintype "input"))
      (node (ref "C27") (pin "2") (pinfunction "2_2") (pintype "input"))
      (node (ref "C29") (pin "1") (pinfunction "1_1") (pintype "input"))
      (node (ref "C30") (pin "2") (pinfunction "2_2") (pintype "input"))
      (node (ref "C32") (pin "2") (pinfunction "2_2") (pintype "input"))
      (node (ref "C34") (pin "1") (pinfunction "1_1") (pintype "input"))
      (node (ref "C35") (pin "1") (pinfunction "1_1") (pintype "input"))
      (node (ref "C38") (pin "1") (pinfunction "1_1") (pintype "input"))
      (node (ref "C5") (pin "1") (pinfunction "1_1") (pintype "input"))
      (node (ref "C6") (pin "1") (pinfunction "1_1") (pintype "input"))
      (node (ref "C7") (pin "1") (pinfunction "1_1") (pintype "input"))
      (node (ref "C8") (pin "1") (pinfunction "1_1") (pintype "input"))
      (node (ref "CN1") (pin "1") (pinfunction "1_1") (pintype "input"))
      (node (ref "CN1") (pin "5") (pinfunction "5_5") (pintype "input"))
      (node (ref "CN2") (pin "1") (pinfunction "1_1") (pintype "input"))
      (node (ref "CN2") (pin "5") (pinfunction "5_5") (pintype "input"))
      (node (ref "CN3") (pin "1") (pinfunction "1_1") (pintype "input"))
      (node (ref "CN3") (pin "5") (pinfunction "5_5") (pintype "input"))
      (node (ref "CN4") (pin "1") (pinfunction "1_1") (pintype "input"))
      (node (ref "CN4") (pin "5") (pinfunction "5_5") (pintype "input"))
      (node (ref "CN5") (pin "1") (pinfunction "1_1") (pintype "input"))
      (node (ref "CN5") (pin "3") (pinfunction "3_3") (pintype "input"))
      (node (ref "CN8") (pin "1") (pinfunction "1_1") (pintype "input"))
      (node (ref "D1") (pin "1") (pinfunction "A_1") (pintype "input"))
      (node (ref "D2") (pin "2") (pinfunction "A_2") (pintype "input"))
      (node (ref "D3") (pin "1") (pinfunction "A_1") (pintype "input"))
      (node (ref "D4") (pin "1") (pinfunction "A_1") (pintype "input"))
      (node (ref "D4") (pin "4") (pinfunction "A_4") (pintype "input"))
      (node (ref "D5") (pin "4") (pinfunction "A_4") (pintype "input"))
      (node (ref "DC1") (pin "2") (pinfunction "2_2") (pintype "input"))
      (node (ref "DC1") (pin "3") (pinfunction "3_3") (pintype "input"))
      (node (ref "DC2") (pin "2") (pinfunction "2_2") (pintype "input"))
      (node (ref "DC2") (pin "3") (pinfunction "3_3") (pintype "input"))
      (node (ref "DC3") (pin "2") (pinfunction "2_2") (pintype "input"))
      (node (ref "DC3") (pin "3") (pinfunction "3_3") (pintype "input"))
      (node (ref "GN0") (pin "1") (pinfunction "1_1") (pintype "unspecified"))
      (node (ref "H1") (pin "2") (pinfunction "2_2") (pintype "input"))
      (node (ref "LED1") (pin "2") (pinfunction "-_2") (pintype "input"))
      (node (ref "LED2") (pin "2") (pinfunction "-_2") (pintype "input"))
      (node (ref "LED4") (pin "2") (pinfunction "-_2") (pintype "input"))
      (node (ref "LED5") (pin "2") (pinfunction "-_2") (pintype "input"))
      (node (ref "Q11") (pin "2") (pinfunction "E_2") (pintype "input"))
      (node (ref "Q15") (pin "2") (pinfunction "E_2") (pintype "input"))
      (node (ref "Q16") (pin "2") (pinfunction "E_2") (pintype "input"))
      (node (ref "Q19") (pin "2") (pinfunction "E_2") (pintype "input"))
      (node (ref "Q20") (pin "2") (pinfunction "E_2") (pintype "input"))
      (node (ref "Q3") (pin "3") (pinfunction "S_3") (pintype "input"))
      (node (ref "Q7") (pin "2") (pinfunction "E_2") (pintype "input"))
      (node (ref "R11") (pin "1") (pinfunction "1_1") (pintype "input"))
      (node (ref "R12") (pin "2") (pinfunction "2_2") (pintype "input"))
      (node (ref "R13") (pin "1") (pinfunction "1_1") (pintype "input"))
      (node (ref "R16") (pin "1") (pinfunction "1_1") (pintype "input"))
      (node (ref "R18") (pin "1") (pinfunction "1_1") (pintype "input"))
      (node (ref "R20") (pin "1") (pinfunction "1_1") (pintype "input"))
      (node (ref "R33") (pin "1") (pinfunction "1_1") (pintype "input"))
      (node (ref "R34") (pin "2") (pinfunction "2_2") (pintype "input"))
      (node (ref "R39") (pin "1") (pinfunction "1_1") (pintype "input"))
      (node (ref "R40") (pin "1") (pinfunction "1_1") (pintype "input"))
      (node (ref "R48") (pin "1") (pinfunction "1_1") (pintype "input"))
      (node (ref "R54") (pin "1") (pinfunction "1_1") (pintype "input"))
      (node (ref "R56") (pin "1") (pinfunction "1_1") (pintype "input"))
      (node (ref "R59") (pin "1") (pinfunction "1_1") (pintype "input"))
      (node (ref "R87") (pin "1") (pinfunction "1_1") (pintype "input"))
      (node (ref "U0") (pin "14") (pinfunction "GND_14") (pintype "unspecified"))
      (node (ref "U0") (pin "20") (pinfunction "GND_20") (pintype "unspecified"))
      (node (ref "U0") (pin "25") (pinfunction "GND_25") (pintype "unspecified"))
      (node (ref "U0") (pin "30") (pinfunction "GND_30") (pintype "unspecified"))
      (node (ref "U0") (pin "34") (pinfunction "GND_34") (pintype "unspecified"))
      (node (ref "U0") (pin "39") (pinfunction "GND_39") (pintype "unspecified"))
      (node (ref "U0") (pin "6") (pinfunction "GND_6") (pintype "unspecified"))
      (node (ref "U0") (pin "9") (pinfunction "GND_9") (pintype "unspecified"))
      (node (ref "U10") (pin "6") (pinfunction "GND_6") (pintype "input"))
      (node (ref "U11") (pin "6") (pinfunction "GND_6") (pintype "input"))
      (node (ref "U12") (pin "7") (pinfunction "GND_7") (pintype "input"))
      (node (ref "U12") (pin "9") (pinfunction "EP_9") (pintype "input"))
      (node (ref "U14") (pin "2") (pinfunction "A0_2") (pintype "input"))
      (node (ref "U14") (pin "6") (pinfunction "GND_6") (pintype "input"))
      (node (ref "U16") (pin "6") (pinfunction "GND_6") (pintype "input"))
      (node (ref "U17") (pin "3") (pinfunction "A2_3") (pintype "input"))
      (node (ref "U17") (pin "4") (pinfunction "VSS_4") (pintype "input"))
      (node (ref "U5") (pin "7") (pinfunction "GND_7") (pintype "input"))
      (node (ref "U5") (pin "9") (pinfunction "EP_9") (pintype "input"))
      (node (ref "U7") (pin "1") (pinfunction "A1_1") (pintype "input"))
      (node (ref "U7") (pin "6") (pinfunction "GND_6") (pintype "input"))
    )
    (net (code "8") (name "GND_IN") (class "Default")
      (node (ref "DC0") (pin "1") (pinfunction "1_1") (pintype "input"))
      (node (ref "Q3") (pin "2") (pinfunction "D_2") (pintype "input"))
    )
    (net (code "9") (name "GPIO13_PWM1") (class "Default")
      (node (ref "R53") (pin "1") (pinfunction "1_1") (pintype "input"))
      (node (ref "U0") (pin "33") (pinfunction "(PWM1)_GPIO13_33") (pintype "unspecified"))
    )
    (net (code "10") (name "GPIO18_PWM0") (class "Default")
      (node (ref "R55") (pin "1") (pinfunction "1_1") (pintype "input"))
      (node (ref "U0") (pin "12") (pinfunction "(PWM0)_GPIO18_12") (pintype "unspecified"))
    )
    (net (code "11") (name "GPIO20") (class "Default")
      (node (ref "R41") (pin "1") (pinfunction "1_1") (pintype "input"))
      (node (ref "U0") (pin "38") (pinfunction "(MOSI)_GPIO20_38") (pintype "unspecified"))
    )
    (net (code "12") (name "GPIO21") (class "Default")
      (node (ref "R49") (pin "1") (pinfunction "1_1") (pintype "input"))
      (node (ref "U0") (pin "40") (pinfunction "(SCLK)_GPIO21_40") (pintype "unspecified"))
    )
    (net (code "13") (name "GPIO26") (class "Default")
      (node (ref "R21") (pin "1") (pinfunction "1_1") (pintype "input"))
      (node (ref "U0") (pin "37") (pinfunction "GPIO26_37") (pintype "unspecified"))
    )
    (net (code "14") (name "ID_SC") (class "Default")
      (node (ref "R90") (pin "1") (pinfunction "1_1") (pintype "input"))
      (node (ref "U0") (pin "28") (pinfunction "(ID_SC)_GPIO1_28") (pintype "unspecified"))
      (node (ref "U17") (pin "6") (pinfunction "SCL_6") (pintype "input"))
    )
    (net (code "15") (name "ID_SD") (class "Default")
      (node (ref "R89") (pin "1") (pinfunction "1_1") (pintype "input"))
      (node (ref "U0") (pin "27") (pinfunction "(ID_SD)_GPIO0_27") (pintype "unspecified"))
      (node (ref "U17") (pin "5") (pinfunction "SDA_5") (pintype "input"))
    )
    (net (code "16") (name "Net-(C12-Pad1)") (class "Default")
      (node (ref "C12") (pin "1") (pinfunction "1_1") (pintype "input"))
      (node (ref "R12") (pin "1") (pinfunction "1_1") (pintype "input"))
    )
    (net (code "17") (name "Net-(C28-Pad1)") (class "Default")
      (node (ref "C28") (pin "1") (pinfunction "1_1") (pintype "input"))
      (node (ref "R34") (pin "1") (pinfunction "1_1") (pintype "input"))
    )
    (net (code "18") (name "Net-(CN7-Pad1)") (class "Default")
      (node (ref "CN7") (pin "1") (pinfunction "1_1") (pintype "input"))
      (node (ref "CN7") (pin "3") (pinfunction "3_3") (pintype "input"))
      (node (ref "R66") (pin "2") (pinfunction "2_2") (pintype "input"))
    )
    (net (code "19") (name "Net-(CN7-Pad4)") (class "Default")
      (node (ref "CN7") (pin "4") (pinfunction "4_4") (pintype "input"))
      (node (ref "R67") (pin "1") (pinfunction "1_1") (pintype "input"))
    )
    (net (code "20") (name "Net-(D1-K)") (class "Default")
      (node (ref "C9") (pin "2") (pinfunction "2_2") (pintype "input"))
      (node (ref "D1") (pin "2") (pinfunction "K_2") (pintype "input"))
      (node (ref "U5") (pin "8") (pinfunction "PH_8") (pintype "input"))
      (node (ref "U6") (pin "1") (pinfunction "1_1") (pintype "input"))
    )
    (net (code "21") (name "Net-(D2-C)") (class "Default")
      (node (ref "D2") (pin "1") (pinfunction "C_1") (pintype "input"))
      (node (ref "Q3") (pin "1") (pinfunction "G_1") (pintype "input"))
      (node (ref "R17") (pin "2") (pinfunction "2_2") (pintype "input"))
      (node (ref "R18") (pin "2") (pinfunction "2_2") (pintype "input"))
    )
    (net (code "22") (name "Net-(D3-K)") (class "Default")
      (node (ref "C25") (pin "2") (pinfunction "2_2") (pintype "input"))
      (node (ref "D3") (pin "2") (pinfunction "K_2") (pintype "input"))
      (node (ref "U12") (pin "8") (pinfunction "PH_8") (pintype "input"))
      (node (ref "U13") (pin "1") (pinfunction "1_1") (pintype "input"))
    )
    (net (code "23") (name "Net-(F5-Pad2)") (class "Default")
      (node (ref "F5") (pin "2") (pinfunction "2_2") (pintype "input"))
      (node (ref "Q4") (pin "5") (pinfunction "D_5") (pintype "input"))
      (node (ref "Q4") (pin "6") (pinfunction "D_6") (pintype "input"))
      (node (ref "Q4") (pin "7") (pinfunction "D_7") (pintype "input"))
      (node (ref "Q4") (pin "8") (pinfunction "D_8") (pintype "input"))
    )
    (net (code "24") (name "Net-(F6-Pad2)") (class "Default")
      (node (ref "F6") (pin "2") (pinfunction "2_2") (pintype "input"))
      (node (ref "Q8") (pin "5") (pinfunction "D_5") (pintype "input"))
      (node (ref "Q8") (pin "6") (pinfunction "D_6") (pintype "input"))
      (node (ref "Q8") (pin "7") (pinfunction "D_7") (pintype "input"))
      (node (ref "Q8") (pin "8") (pinfunction "D_8") (pintype "input"))
    )
    (net (code "25") (name "Net-(F7-Pad2)") (class "Default")
      (node (ref "F7") (pin "2") (pinfunction "2_2") (pintype "input"))
      (node (ref "Q9") (pin "5") (pinfunction "D_5") (pintype "input"))
      (node (ref "Q9") (pin "6") (pinfunction "D_6") (pintype "input"))
      (node (ref "Q9") (pin "7") (pinfunction "D_7") (pintype "input"))
      (node (ref "Q9") (pin "8") (pinfunction "D_8") (pintype "input"))
    )
    (net (code "26") (name "Net-(F8-Pad2)") (class "Default")
      (node (ref "F8") (pin "2") (pinfunction "2_2") (pintype "input"))
      (node (ref "Q10") (pin "5") (pinfunction "D_5") (pintype "input"))
      (node (ref "Q10") (pin "6") (pinfunction "D_6") (pintype "input"))
      (node (ref "Q10") (pin "7") (pinfunction "D_7") (pintype "input"))
      (node (ref "Q10") (pin "8") (pinfunction "D_8") (pintype "input"))
    )
    (net (code "27") (name "Net-(F10-Pad2)") (class "Default")
      (node (ref "F10") (pin "2") (pinfunction "2_2") (pintype "input"))
      (node (ref "Q14") (pin "5") (pinfunction "D_5") (pintype "input"))
      (node (ref "Q14") (pin "6") (pinfunction "D_6") (pintype "input"))
      (node (ref "Q14") (pin "7") (pinfunction "D_7") (pintype "input"))
      (node (ref "Q14") (pin "8") (pinfunction "D_8") (pintype "input"))
    )
    (net (code "28") (name "Net-(LED1-+)") (class "Default")
      (node (ref "LED1") (pin "1") (pinfunction "+_1") (pintype "input"))
      (node (ref "R61") (pin "2") (pinfunction "2_2") (pintype "input"))
    )
    (net (code "29") (name "Net-(LED2-+)") (class "Default")
      (node (ref "LED2") (pin "1") (pinfunction "+_1") (pintype "input"))
      (node (ref "R62") (pin "2") (pinfunction "2_2") (pintype "input"))
    )
    (net (code "30") (name "Net-(LED4-+)") (class "Default")
      (node (ref "LED4") (pin "1") (pinfunction "+_1") (pintype "input"))
      (node (ref "R64") (pin "2") (pinfunction "2_2") (pintype "input"))
    )
    (net (code "31") (name "Net-(LED5-+)") (class "Default")
      (node (ref "LED5") (pin "1") (pinfunction "+_1") (pintype "input"))
      (node (ref "R65") (pin "2") (pinfunction "2_2") (pintype "input"))
    )
    (net (code "32") (name "Net-(LED13-+)") (class "Default")
      (node (ref "LED13") (pin "1") (pinfunction "+_1") (pintype "input"))
      (node (ref "R88") (pin "2") (pinfunction "2_2") (pintype "input"))
    )
    (net (code "33") (name "Net-(LED13--)") (class "Default")
      (node (ref "LED13") (pin "2") (pinfunction "-_2") (pintype "input"))
      (node (ref "Q19") (pin "3") (pinfunction "C_3") (pintype "input"))
    )
    (net (code "34") (name "Net-(Q1-B1)") (class "Default")
      (node (ref "Q1") (pin "1") (pinfunction "C1_1") (pintype "input"))
      (node (ref "Q1") (pin "2") (pinfunction "B1_2") (pintype "input"))
      (node (ref "Q1") (pin "3") (pinfunction "B2_3") (pintype "input"))
      (node (ref "R16") (pin "2") (pinfunction "2_2") (pintype "input"))
    )
    (net (code "35") (name "Net-(Q1-C2)") (class "Default")
      (node (ref "Q1") (pin "4") (pinfunction "C2_4") (pintype "input"))
      (node (ref "Q2") (pin "1") (pinfunction "G_1") (pintype "input"))
      (node (ref "R59") (pin "2") (pinfunction "2_2") (pintype "input"))
    )
    (net (code "36") (name "Net-(Q4-G)") (class "Default")
      (node (ref "Q4") (pin "4") (pinfunction "G_4") (pintype "input"))
      (node (ref "Q7") (pin "3") (pinfunction "C_3") (pintype "input"))
      (node (ref "R22") (pin "1") (pinfunction "1_1") (pintype "input"))
    )
    (net (code "37") (name "Net-(Q7-B)") (class "Default")
      (node (ref "Q7") (pin "1") (pinfunction "B_1") (pintype "input"))
      (node (ref "R20") (pin "2") (pinfunction "2_2") (pintype "input"))
      (node (ref "R21") (pin "2") (pinfunction "2_2") (pintype "input"))
    )
    (net (code "38") (name "Net-(Q10-G)") (class "Default")
      (node (ref "Q10") (pin "4") (pinfunction "G_4") (pintype "input"))
      (node (ref "Q11") (pin "3") (pinfunction "C_3") (pintype "input"))
      (node (ref "R42") (pin "1") (pinfunction "1_1") (pintype "input"))
    )
    (net (code "39") (name "Net-(Q11-B)") (class "Default")
      (node (ref "Q11") (pin "1") (pinfunction "B_1") (pintype "input"))
      (node (ref "R40") (pin "2") (pinfunction "2_2") (pintype "input"))
      (node (ref "R41") (pin "2") (pinfunction "2_2") (pintype "input"))
    )
    (net (code "40") (name "Net-(Q14-G)") (class "Default")
      (node (ref "Q14") (pin "4") (pinfunction "G_4") (pintype "input"))
      (node (ref "Q15") (pin "3") (pinfunction "C_3") (pintype "input"))
      (node (ref "R50") (pin "1") (pinfunction "1_1") (pintype "input"))
    )
    (net (code "41") (name "Net-(Q15-B)") (class "Default")
      (node (ref "Q15") (pin "1") (pinfunction "B_1") (pintype "input"))
      (node (ref "R48") (pin "2") (pinfunction "2_2") (pintype "input"))
      (node (ref "R49") (pin "2") (pinfunction "2_2") (pintype "input"))
    )
    (net (code "42") (name "Net-(Q16-B)") (class "Default")
      (node (ref "Q16") (pin "1") (pinfunction "B_1") (pintype "input"))
      (node (ref "R53") (pin "2") (pinfunction "2_2") (pintype "input"))
      (node (ref "R54") (pin "2") (pinfunction "2_2") (pintype "input"))
    )
    (net (code "43") (name "Net-(Q16-C)") (class "Default")
      (node (ref "Q16") (pin "3") (pinfunction "C_3") (pintype "input"))
      (node (ref "Q8") (pin "4") (pinfunction "G_4") (pintype "input"))
      (node (ref "R27") (pin "1") (pinfunction "1_1") (pintype "input"))
    )
    (net (code "44") (name "Net-(Q19-B)") (class "Default")
      (node (ref "Q19") (pin "1") (pinfunction "B_1") (pintype "input"))
      (node (ref "R86") (pin "1") (pinfunction "1_1") (pintype "input"))
      (node (ref "R87") (pin "2") (pinfunction "2_2") (pintype "input"))
    )
    (net (code "45") (name "Net-(Q20-B)") (class "Default")
      (node (ref "Q20") (pin "1") (pinfunction "B_1") (pintype "input"))
      (node (ref "R55") (pin "2") (pinfunction "2_2") (pintype "input"))
      (node (ref "R56") (pin "2") (pinfunction "2_2") (pintype "input"))
    )
    (net (code "46") (name "Net-(Q20-C)") (class "Default")
      (node (ref "Q20") (pin "3") (pinfunction "C_3") (pintype "input"))
      (node (ref "Q9") (pin "4") (pinfunction "G_4") (pintype "input"))
      (node (ref "R30") (pin "1") (pinfunction "1_1") (pintype "input"))
    )
    (net (code "47") (name "Net-(U5-BOOT)") (class "Default")
      (node (ref "C9") (pin "1") (pinfunction "1_1") (pintype "input"))
      (node (ref "U5") (pin "1") (pinfunction "BOOT_1") (pintype "input"))
    )
    (net (code "48") (name "Net-(U5-COMP)") (class "Default")
      (node (ref "C12") (pin "2") (pinfunction "2_2") (pintype "input"))
      (node (ref "C13") (pin "2") (pinfunction "2_2") (pintype "input"))
      (node (ref "U5") (pin "6") (pinfunction "COMP_6") (pintype "input"))
    )
    (net (code "49") (name "Net-(U5-EN)") (class "Default")
      (node (ref "R10") (pin "1") (pinfunction "1_1") (pintype "input"))
      (node (ref "R11") (pin "2") (pinfunction "2_2") (pintype "input"))
      (node (ref "U5") (pin "3") (pinfunction "EN_3") (pintype "input"))
    )
    (net (code "50") (name "Net-(U5-SS)") (class "Default")
      (node (ref "C8") (pin "2") (pinfunction "2_2") (pintype "input"))
      (node (ref "U5") (pin "4") (pinfunction "SS_4") (pintype "input"))
    )
    (net (code "51") (name "Net-(U5-VSENSE)") (class "Default")
      (node (ref "R13") (pin "2") (pinfunction "2_2") (pintype "input"))
      (node (ref "R14") (pin "1") (pinfunction "1_1") (pintype "input"))
      (node (ref "U5") (pin "5") (pinfunction "VSENSE_5") (pintype "input"))
    )
    (net (code "52") (name "Net-(U7-VIN+)") (class "Default")
      (node (ref "F5") (pin "1") (pinfunction "1_1") (pintype "input"))
      (node (ref "R23") (pin "2") (pinfunction "2_2") (pintype "input"))
      (node (ref "U7") (pin "8") (pinfunction "VIN+_8") (pintype "input"))
    )
    (net (code "53") (name "Net-(U7-VIN-)") (class "Default")
      (node (ref "DC1") (pin "1") (pinfunction "1_1") (pintype "input"))
      (node (ref "R23") (pin "1") (pinfunction "1_1") (pintype "input"))
      (node (ref "R61") (pin "1") (pinfunction "1_1") (pintype "input"))
      (node (ref "U7") (pin "7") (pinfunction "VIN-_7") (pintype "input"))
    )
    (net (code "54") (name "Net-(U10-VIN+)") (class "Default")
      (node (ref "F6") (pin "1") (pinfunction "1_1") (pintype "input"))
      (node (ref "R26") (pin "2") (pinfunction "2_2") (pintype "input"))
      (node (ref "U10") (pin "8") (pinfunction "VIN+_8") (pintype "input"))
    )
    (net (code "55") (name "Net-(U10-VIN-)") (class "Default")
      (node (ref "AV1") (pin "2") (pinfunction "2_2") (pintype "input"))
      (node (ref "R26") (pin "1") (pinfunction "1_1") (pintype "input"))
      (node (ref "R64") (pin "1") (pinfunction "1_1") (pintype "input"))
      (node (ref "U10") (pin "7") (pinfunction "VIN-_7") (pintype "input"))
    )
    (net (code "56") (name "Net-(U11-VIN+)") (class "Default")
      (node (ref "F7") (pin "1") (pinfunction "1_1") (pintype "input"))
      (node (ref "R29") (pin "2") (pinfunction "2_2") (pintype "input"))
      (node (ref "U11") (pin "8") (pinfunction "VIN+_8") (pintype "input"))
    )
    (net (code "57") (name "Net-(U11-VIN-)") (class "Default")
      (node (ref "AV0") (pin "2") (pinfunction "2_2") (pintype "input"))
      (node (ref "R29") (pin "1") (pinfunction "1_1") (pintype "input"))
      (node (ref "R65") (pin "1") (pinfunction "1_1") (pintype "input"))
      (node (ref "U11") (pin "7") (pinfunction "VIN-_7") (pintype "input"))
    )
    (net (code "58") (name "Net-(U12-BOOT)") (class "Default")
      (node (ref "C25") (pin "1") (pinfunction "1_1") (pintype "input"))
      (node (ref "U12") (pin "1") (pinfunction "BOOT_1") (pintype "input"))
    )
    (net (code "59") (name "Net-(U12-COMP)") (class "Default")
      (node (ref "C28") (pin "2") (pinfunction "2_2") (pintype "input"))
      (node (ref "C29") (pin "2") (pinfunction "2_2") (pintype "input"))
      (node (ref "U12") (pin "6") (pinfunction "COMP_6") (pintype "input"))
    )
    (net (code "60") (name "Net-(U12-EN)") (class "Default")
      (node (ref "CN8") (pin "2") (pinfunction "2_2") (pintype "input"))
      (node (ref "R32") (pin "1") (pinfunction "1_1") (pintype "input"))
      (node (ref "R33") (pin "2") (pinfunction "2_2") (pintype "input"))
      (node (ref "U12") (pin "3") (pinfunction "EN_3") (pintype "input"))
    )
    (net (code "61") (name "Net-(U12-SS)") (class "Default")
      (node (ref "C24") (pin "2") (pinfunction "2_2") (pintype "input"))
      (node (ref "U12") (pin "4") (pinfunction "SS_4") (pintype "input"))
    )
    (net (code "62") (name "Net-(U12-VSENSE)") (class "Default")
      (node (ref "R39") (pin "2") (pinfunction "2_2") (pintype "input"))
      (node (ref "R66") (pin "1") (pinfunction "1_1") (pintype "input"))
      (node (ref "U12") (pin "5") (pinfunction "VSENSE_5") (pintype "input"))
    )
    (net (code "63") (name "Net-(U14-VIN+)") (class "Default")
      (node (ref "F8") (pin "1") (pinfunction "1_1") (pintype "input"))
      (node (ref "R43") (pin "2") (pinfunction "2_2") (pintype "input"))
      (node (ref "U14") (pin "8") (pinfunction "VIN+_8") (pintype "input"))
    )
    (net (code "64") (name "Net-(U14-VIN-)") (class "Default")
      (node (ref "DC2") (pin "1") (pinfunction "1_1") (pintype "input"))
      (node (ref "R43") (pin "1") (pinfunction "1_1") (pintype "input"))
      (node (ref "R62") (pin "1") (pinfunction "1_1") (pintype "input"))
      (node (ref "U14") (pin "7") (pinfunction "VIN-_7") (pintype "input"))
    )
    (net (code "65") (name "Net-(U16-VIN+)") (class "Default")
      (node (ref "F10") (pin "1") (pinfunction "1_1") (pintype "input"))
      (node (ref "R51") (pin "2") (pinfunction "2_2") (pintype "input"))
      (node (ref "U16") (pin "8") (pinfunction "VIN+_8") (pintype "input"))
    )
    (net (code "66") (name "Net-(U16-VIN-)") (class "Default")
      (node (ref "DC3") (pin "1") (pinfunction "1_1") (pintype "input"))
      (node (ref "R51") (pin "1") (pinfunction "1_1") (pintype "input"))
      (node (ref "R86") (pin "2") (pinfunction "2_2") (pintype "input"))
      (node (ref "U16") (pin "7") (pinfunction "VIN-_7") (pintype "input"))
    )
    (net (code "67") (name "Net-(U17-WP)") (class "Default")
      (node (ref "R91") (pin "1") (pinfunction "1_1") (pintype "input"))
      (node (ref "U17") (pin "7") (pinfunction "WP_7") (pintype "input"))
      (node (ref "WP0") (pin "1") (pinfunction "1_1") (pintype "unspecified"))
    )
    (net (code "68") (name "PPS") (class "Default")
      (node (ref "H1") (pin "5") (pinfunction "5_5") (pintype "input"))
      (node (ref "U0") (pin "22") (pinfunction "GPIO25_22") (pintype "unspecified"))
    )
    (net (code "69") (name "RXD") (class "Default")
      (node (ref "H1") (pin "3") (pinfunction "3_3") (pintype "input"))
      (node (ref "U0") (pin "10") (pinfunction "(RXD)_GPIO15_10") (pintype "unspecified"))
    )
    (net (code "70") (name "SCL") (class "Default")
      (node (ref "CN1") (pin "2") (pinfunction "2_2") (pintype "input"))
      (node (ref "CN1") (pin "6") (pinfunction "6_6") (pintype "input"))
      (node (ref "CN2") (pin "2") (pinfunction "2_2") (pintype "input"))
      (node (ref "CN2") (pin "6") (pinfunction "6_6") (pintype "input"))
      (node (ref "D4") (pin "3") (pinfunction "AC_3") (pintype "input"))
      (node (ref "R7") (pin "1") (pinfunction "1_1") (pintype "input"))
      (node (ref "U0") (pin "5") (pinfunction "(SCL)_GPIO3_5") (pintype "unspecified"))
      (node (ref "U10") (pin "4") (pinfunction "SCL_4") (pintype "input"))
      (node (ref "U11") (pin "1") (pinfunction "A1_1") (pintype "input"))
      (node (ref "U11") (pin "4") (pinfunction "SCL_4") (pintype "input"))
      (node (ref "U14") (pin "4") (pinfunction "SCL_4") (pintype "input"))
      (node (ref "U16") (pin "4") (pinfunction "SCL_4") (pintype "input"))
      (node (ref "U7") (pin "4") (pinfunction "SCL_4") (pintype "input"))
    )
    (net (code "71") (name "SDA") (class "Default")
      (node (ref "CN1") (pin "3") (pinfunction "3_3") (pintype "input"))
      (node (ref "CN1") (pin "7") (pinfunction "7_7") (pintype "input"))
      (node (ref "CN2") (pin "3") (pinfunction "3_3") (pintype "input"))
      (node (ref "CN2") (pin "7") (pinfunction "7_7") (pintype "input"))
      (node (ref "D4") (pin "6") (pinfunction "AC_6") (pintype "input"))
      (node (ref "R6") (pin "1") (pinfunction "1_1") (pintype "input"))
      (node (ref "U0") (pin "3") (pinfunction "(SDA)_GPIO2_3") (pintype "unspecified"))
      (node (ref "U10") (pin "1") (pinfunction "A1_1") (pintype "input"))
      (node (ref "U10") (pin "3") (pinfunction "SDA_3") (pintype "input"))
      (node (ref "U11") (pin "3") (pinfunction "SDA_3") (pintype "input"))
      (node (ref "U14") (pin "3") (pinfunction "SDA_3") (pintype "input"))
      (node (ref "U16") (pin "2") (pinfunction "A0_2") (pintype "input"))
      (node (ref "U16") (pin "3") (pinfunction "SDA_3") (pintype "input"))
      (node (ref "U7") (pin "3") (pinfunction "SDA_3") (pintype "input"))
    )
    (net (code "72") (name "TXD") (class "Default")
      (node (ref "H1") (pin "4") (pinfunction "4_4") (pintype "input"))
      (node (ref "U0") (pin "8") (pinfunction "(TXD)_GPIO14_8") (pintype "unspecified"))
    )
    (net (code "73") (name "VS") (class "Default")
      (node (ref "CN5") (pin "4") (pinfunction "4_4") (pintype "input"))
      (node (ref "CN6") (pin "2") (pinfunction "2_2") (pintype "input"))
      (node (ref "Q14") (pin "1") (pinfunction "S_1") (pintype "input"))
      (node (ref "Q14") (pin "2") (pinfunction "S_2") (pintype "input"))
      (node (ref "Q14") (pin "3") (pinfunction "S_3") (pintype "input"))
      (node (ref "R50") (pin "2") (pinfunction "2_2") (pintype "input"))
    )
    (net (code "74") (name "unconnected-(CN3-Pad2)") (class "Default")
      (node (ref "CN3") (pin "2") (pinfunction "2_2") (pintype "input+no_connect"))
    )
    (net (code "75") (name "unconnected-(CN3-Pad6)") (class "Default")
      (node (ref "CN3") (pin "6") (pinfunction "6_6") (pintype "input+no_connect"))
    )
    (net (code "76") (name "unconnected-(CN4-Pad2)") (class "Default")
      (node (ref "CN4") (pin "2") (pinfunction "2_2") (pintype "input+no_connect"))
    )
    (net (code "77") (name "unconnected-(CN4-Pad6)") (class "Default")
      (node (ref "CN4") (pin "6") (pinfunction "6_6") (pintype "input+no_connect"))
    )
    (net (code "78") (name "unconnected-(CN6-Pad3)") (class "Default")
      (node (ref "CN6") (pin "3") (pinfunction "3_3") (pintype "input+no_connect"))
    )
    (net (code "79") (name "unconnected-(D5-A-Pad1)") (class "Default")
      (node (ref "D5") (pin "1") (pinfunction "A_1") (pintype "input+no_connect"))
    )
    (net (code "80") (name "unconnected-(D5-AC-Pad6)") (class "Default")
      (node (ref "D5") (pin "6") (pinfunction "AC_6") (pintype "input+no_connect"))
    )
    (net (code "81") (name "unconnected-(D5-C-Pad2)") (class "Default")
      (node (ref "D5") (pin "2") (pinfunction "C_2") (pintype "input+no_connect"))
    )
    (net (code "82") (name "unconnected-(DC0-Pad3)") (class "Default")
      (node (ref "DC0") (pin "3") (pinfunction "3_3") (pintype "input+no_connect"))
    )
    (net (code "83") (name "unconnected-(DC0-Pad4)") (class "Default")
      (node (ref "DC0") (pin "4") (pinfunction "4_4") (pintype "input+no_connect"))
    )
    (net (code "84") (name "unconnected-(U0-(CE0)_GPIO8-Pad24)") (class "Default")
      (node (ref "U0") (pin "24") (pinfunction "(CE0)_GPIO8_24") (pintype "unspecified+no_connect"))
    )
    (net (code "85") (name "unconnected-(U0-(CE1)_GPIO7-Pad26)") (class "Default")
      (node (ref "U0") (pin "26") (pinfunction "(CE1)_GPIO7_26") (pintype "unspecified+no_connect"))
    )
    (net (code "86") (name "unconnected-(U0-(MISO)_GPIO9-Pad21)") (class "Default")
      (node (ref "U0") (pin "21") (pinfunction "(MISO)_GPIO9_21") (pintype "unspecified+no_connect"))
    )
    (net (code "87") (name "unconnected-(U0-(MISO)_GPIO19-Pad35)") (class "Default")
      (node (ref "U0") (pin "35") (pinfunction "(MISO)_GPIO19_35") (pintype "unspecified+no_connect"))
    )
    (net (code "88") (name "unconnected-(U0-(MOSI)_GPIO10-Pad19)") (class "Default")
      (node (ref "U0") (pin "19") (pinfunction "(MOSI)_GPIO10_19") (pintype "unspecified+no_connect"))
    )
    (net (code "89") (name "unconnected-(U0-(PWM0)_GPIO12-Pad32)") (class "Default")
      (node (ref "U0") (pin "32") (pinfunction "(PWM0)_GPIO12_32") (pintype "unspecified+no_connect"))
    )
    (net (code "90") (name "unconnected-(U0-(SCLK)_GPIO11-Pad23)") (class "Default")
      (node (ref "U0") (pin "23") (pinfunction "(SCLK)_GPIO11_23") (pintype "unspecified+no_connect"))
    )
    (net (code "91") (name "unconnected-(U0-GPIO5-Pad29)") (class "Default")
      (node (ref "U0") (pin "29") (pinfunction "GPIO5_29") (pintype "unspecified+no_connect"))
    )
    (net (code "92") (name "unconnected-(U0-GPIO6-Pad31)") (class "Default")
      (node (ref "U0") (pin "31") (pinfunction "GPIO6_31") (pintype "unspecified+no_connect"))
    )
    (net (code "93") (name "unconnected-(U0-GPIO16-Pad36)") (class "Default")
      (node (ref "U0") (pin "36") (pinfunction "GPIO16_36") (pintype "unspecified+no_connect"))
    )
    (net (code "94") (name "unconnected-(U0-GPIO17-Pad11)") (class "Default")
      (node (ref "U0") (pin "11") (pinfunction "GPIO17_11") (pintype "unspecified+no_connect"))
    )
    (net (code "95") (name "unconnected-(U0-GPIO22-Pad15)") (class "Default")
      (node (ref "U0") (pin "15") (pinfunction "GPIO22_15") (pintype "unspecified+no_connect"))
    )
    (net (code "96") (name "unconnected-(U0-GPIO23-Pad16)") (class "Default")
      (node (ref "U0") (pin "16") (pinfunction "GPIO23_16") (pintype "unspecified+no_connect"))
    )
    (net (code "97") (name "unconnected-(U0-GPIO24-Pad18)") (class "Default")
      (node (ref "U0") (pin "18") (pinfunction "GPIO24_18") (pintype "unspecified+no_connect"))
    )
    (net (code "98") (name "unconnected-(U0-GPIO27-Pad13)") (class "Default")
      (node (ref "U0") (pin "13") (pinfunction "GPIO27_13") (pintype "unspecified+no_connect"))
    )
    (net (code "99") (name "unconnected-(U17-A0-Pad1)") (class "Default")
      (node (ref "U17") (pin "1") (pinfunction "A0_1") (pintype "input+no_connect"))
    )
    (net (code "100") (name "unconnected-(U17-A1-Pad2)") (class "Default")
      (node (ref "U17") (pin "2") (pinfunction "A1_2") (pintype "input+no_connect"))
    )
  )
)
